# Controller-Board_Rack-PDU_1_0.net
KiCad netlist of a schematic drawn in EAGLE
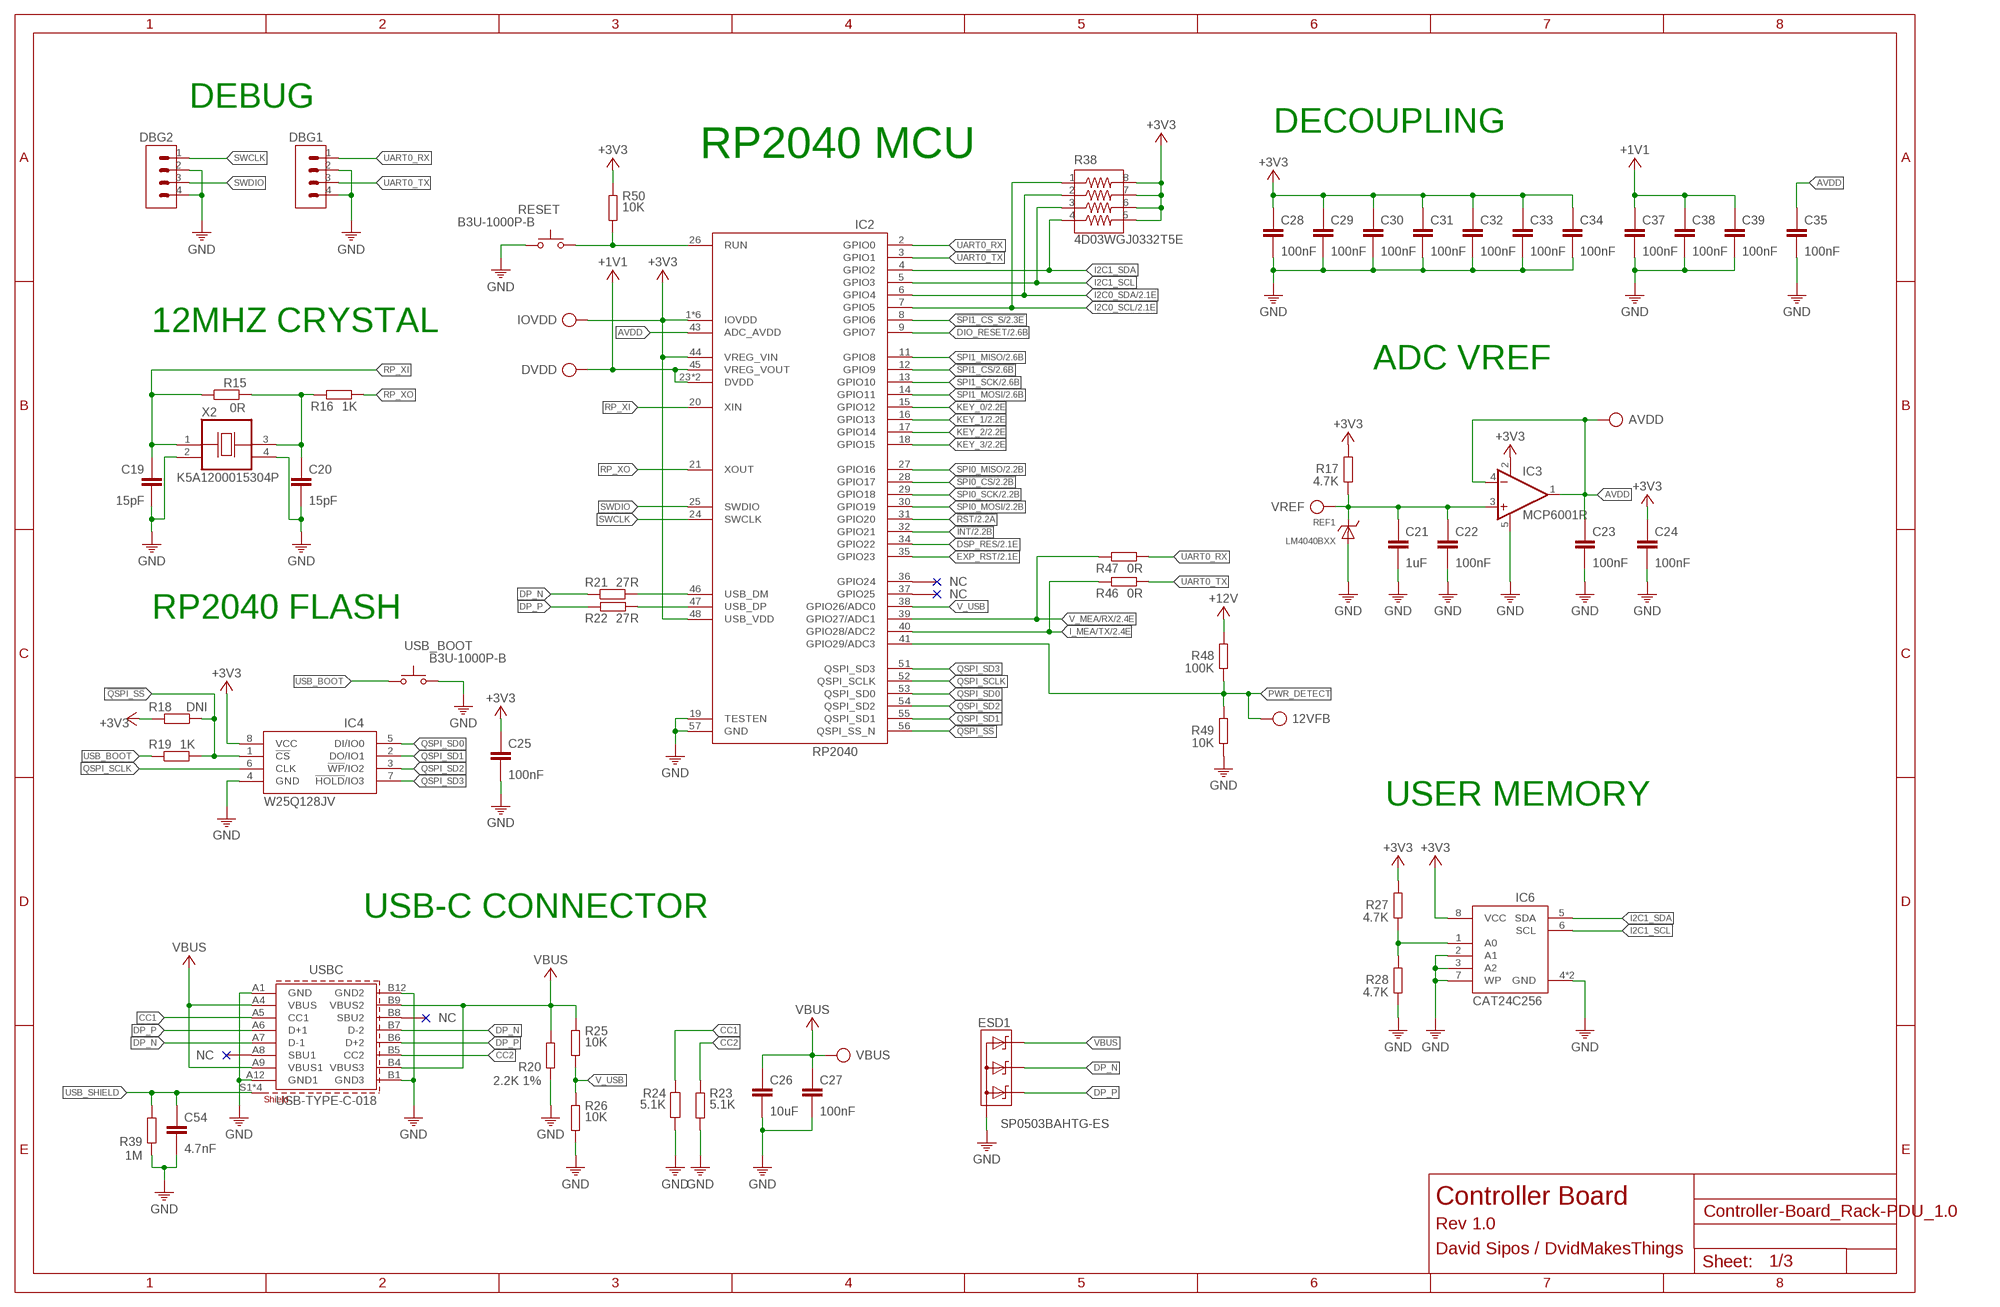
[diagram p0: schematic, sheet 1]
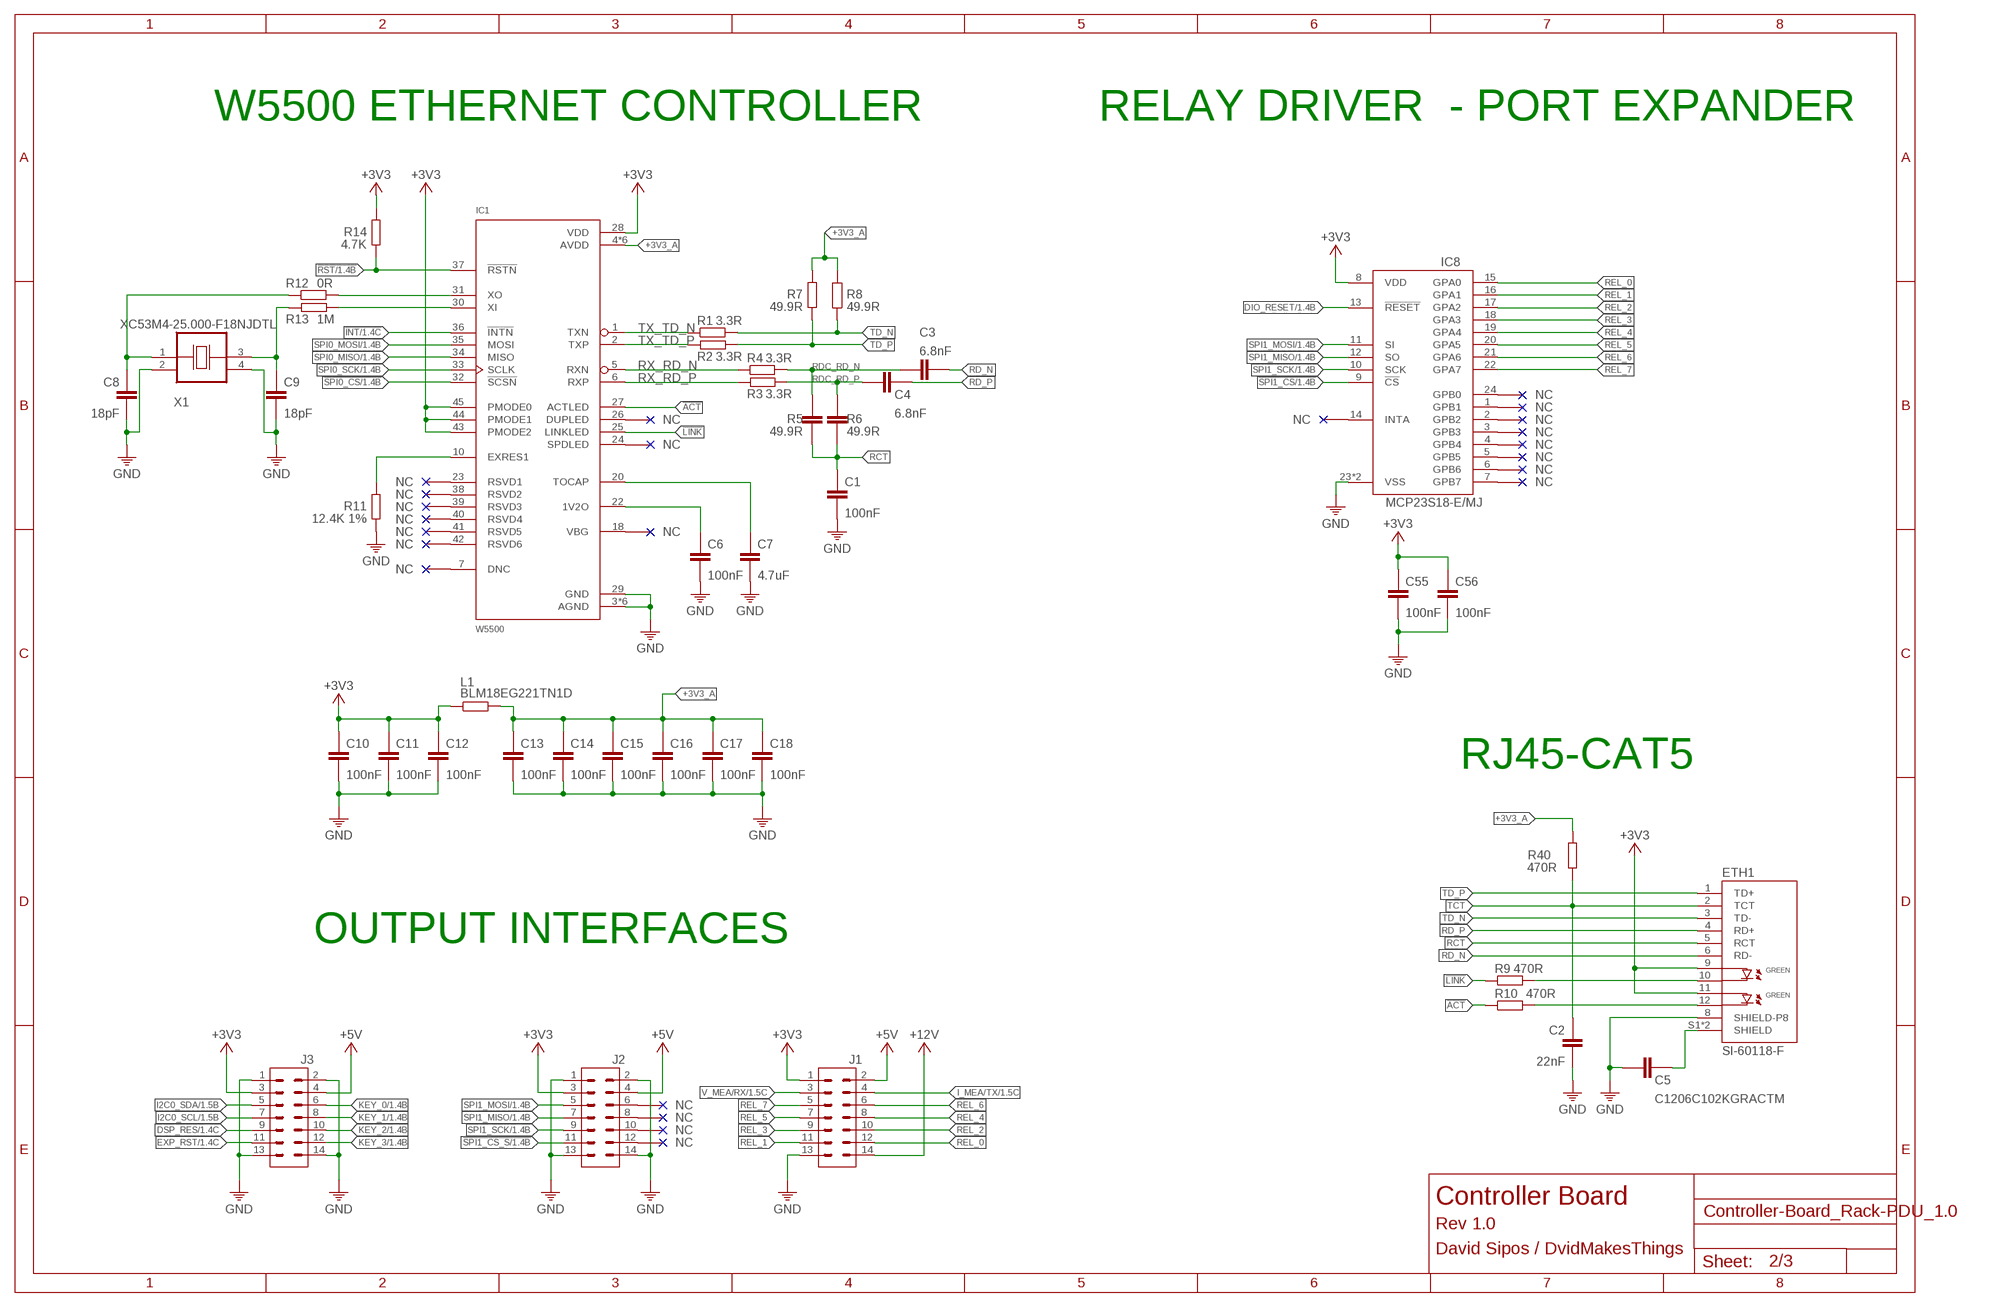
[diagram p1: schematic, sheet 2]
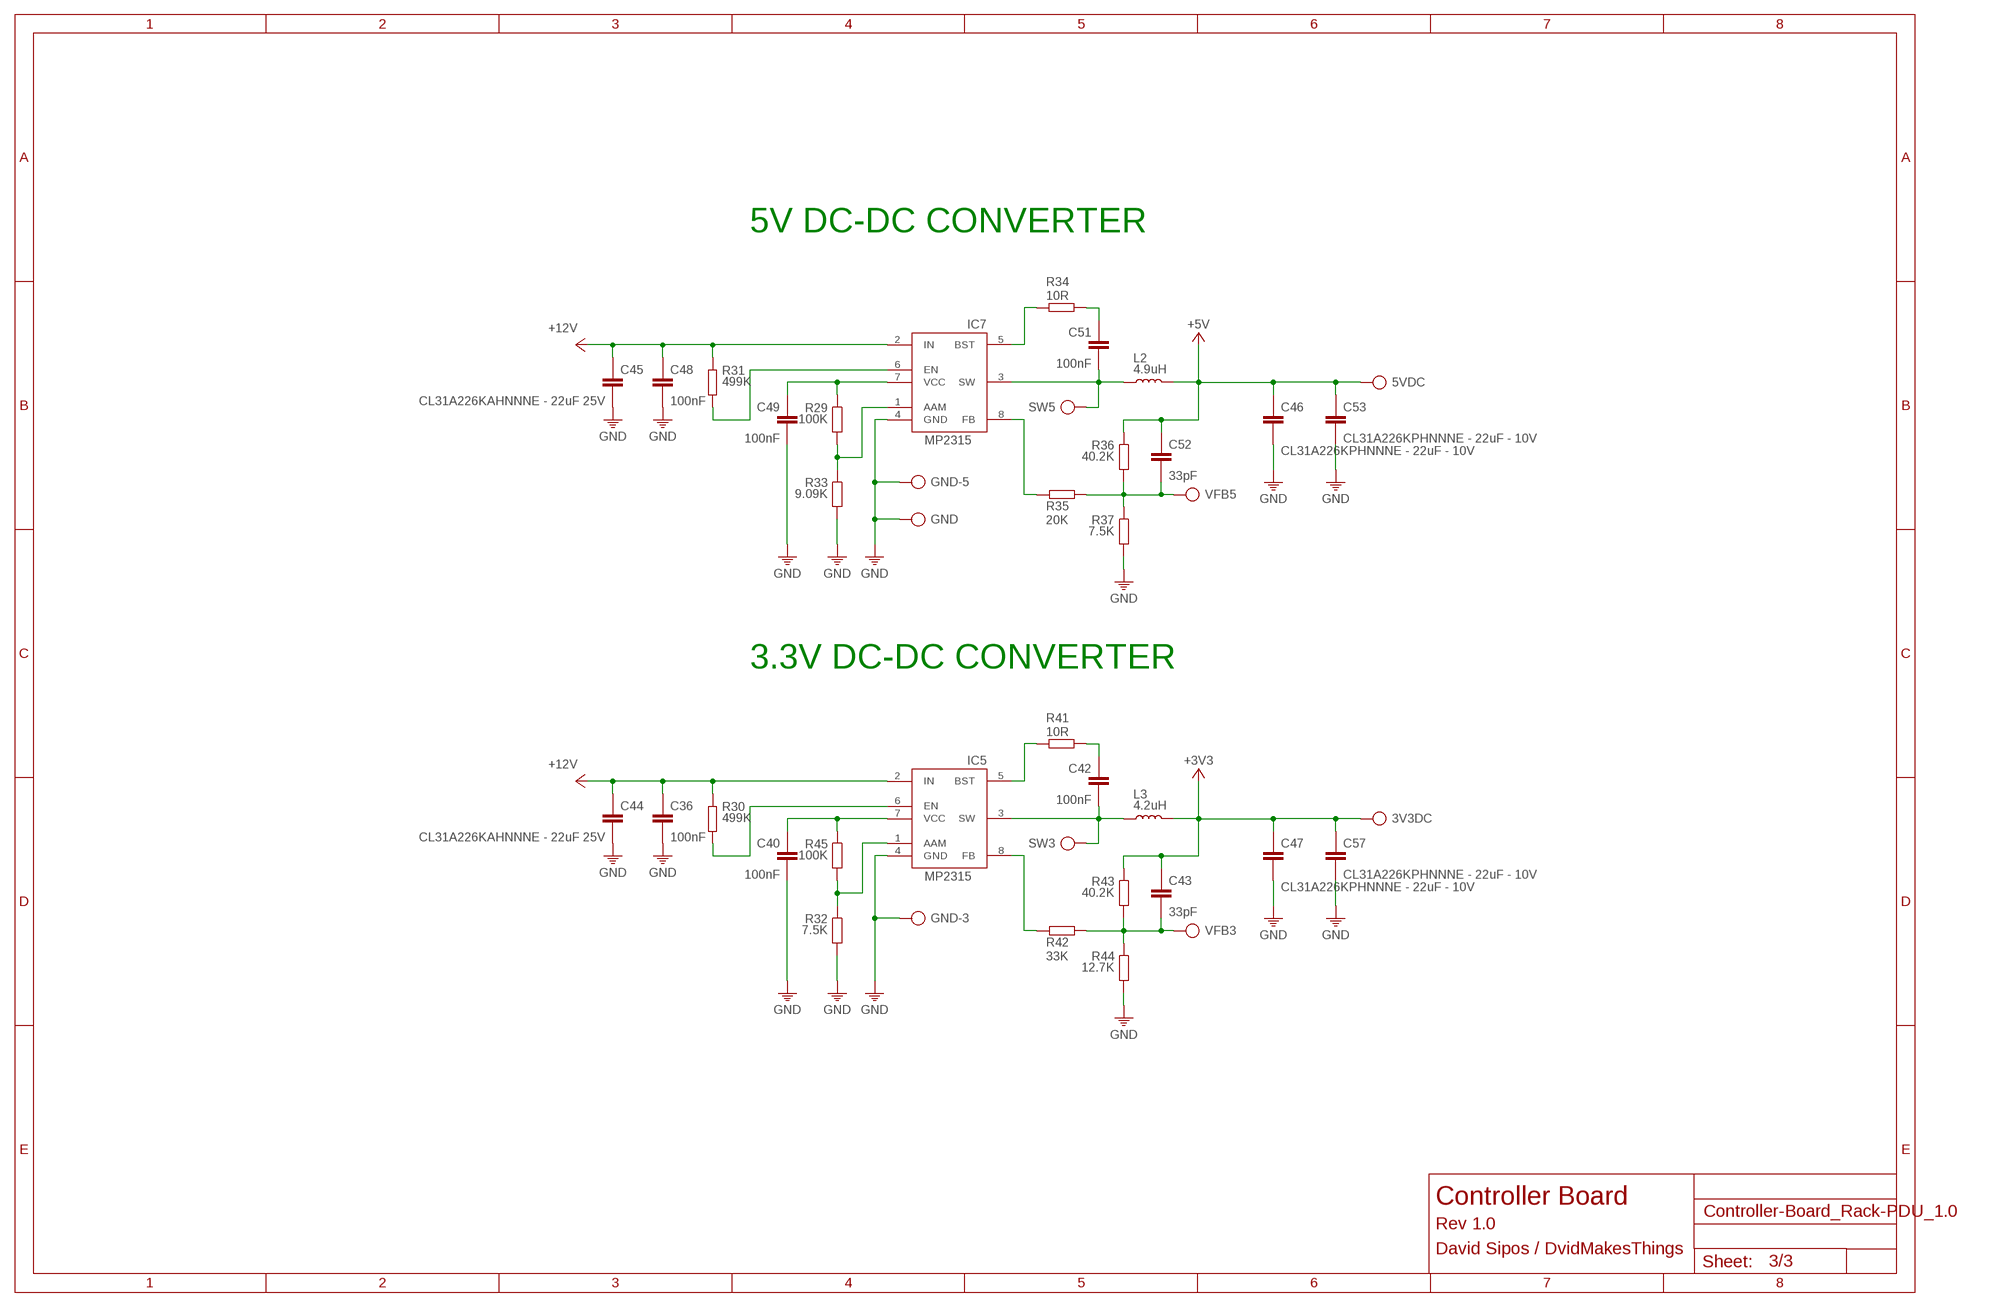
[diagram p2: schematic, sheet 3]

(export (version "E")
  (design (tool "Eeschema 10.0.6"))
  (components
    (comp (ref "C1")
      (value "100nF")
      (footprint "eagle-import:C0402")
      (libsource (lib "eagle-import") (part "C-0402"))
    )
    (comp (ref "C2")
      (value "22nF")
      (footprint "eagle-import:C0402")
      (libsource (lib "eagle-import") (part "C-0402"))
    )
    (comp (ref "C3")
      (value "6.8nF")
      (footprint "eagle-import:C0402")
      (libsource (lib "eagle-import") (part "C-0402"))
    )
    (comp (ref "C4")
      (value "6.8nF")
      (footprint "eagle-import:C0402")
      (libsource (lib "eagle-import") (part "C-0402"))
    )
    (comp (ref "C5")
      (value "C1206C102KGRACTM")
      (footprint "eagle-import:C1206")
      (libsource (lib "eagle-import") (part "C-1206"))
    )
    (comp (ref "C6")
      (value "100nF")
      (footprint "eagle-import:C0402")
      (libsource (lib "eagle-import") (part "C-0402"))
    )
    (comp (ref "C7")
      (value "4.7uF")
      (footprint "eagle-import:C0402")
      (libsource (lib "eagle-import") (part "C-0402"))
    )
    (comp (ref "C8")
      (value "18pF")
      (footprint "eagle-import:C0402")
      (libsource (lib "eagle-import") (part "C-0402"))
    )
    (comp (ref "C9")
      (value "18pF")
      (footprint "eagle-import:C0402")
      (libsource (lib "eagle-import") (part "C-0402"))
    )
    (comp (ref "C10")
      (value "100nF")
      (footprint "eagle-import:C0402")
      (libsource (lib "eagle-import") (part "C-0402"))
    )
    (comp (ref "C11")
      (value "100nF")
      (footprint "eagle-import:C0402")
      (libsource (lib "eagle-import") (part "C-0402"))
    )
    (comp (ref "C12")
      (value "100nF")
      (footprint "eagle-import:C0402")
      (libsource (lib "eagle-import") (part "C-0402"))
    )
    (comp (ref "C13")
      (value "100nF")
      (footprint "eagle-import:C0402")
      (libsource (lib "eagle-import") (part "C-0402"))
    )
    (comp (ref "C14")
      (value "100nF")
      (footprint "eagle-import:C0402")
      (libsource (lib "eagle-import") (part "C-0402"))
    )
    (comp (ref "C15")
      (value "100nF")
      (footprint "eagle-import:C0402")
      (libsource (lib "eagle-import") (part "C-0402"))
    )
    (comp (ref "C16")
      (value "100nF")
      (footprint "eagle-import:C0402")
      (libsource (lib "eagle-import") (part "C-0402"))
    )
    (comp (ref "C17")
      (value "100nF")
      (footprint "eagle-import:C0402")
      (libsource (lib "eagle-import") (part "C-0402"))
    )
    (comp (ref "C18")
      (value "100nF")
      (footprint "eagle-import:C0402")
      (libsource (lib "eagle-import") (part "C-0402"))
    )
    (comp (ref "C55")
      (value "100nF")
      (footprint "eagle-import:C0402")
      (libsource (lib "eagle-import") (part "C-0402"))
    )
    (comp (ref "C56")
      (value "100nF")
      (footprint "eagle-import:C0402")
      (libsource (lib "eagle-import") (part "C-0402"))
    )
    (comp (ref "ETH1")
      (value "SI-60118-F")
      (footprint "eagle-import:RJ45-CAT5")
      (fields (field (name "MANUFACTURER") "Bel Fuse"))
      (libsource (lib "eagle-import") (part "RJ45-CAT5"))
    )
    (comp (ref "IC1")
      (value "W5500")
      (footprint "eagle-import:LQFP48")
      (libsource (lib "eagle-import") (part "W5500"))
    )
    (comp (ref "IC8")
      (value "MCP23S18-E/MJ")
      (footprint "eagle-import:QFN50P400X400X100-25T265")
      (libsource (lib "eagle-import") (part "MCP23S18"))
    )
    (comp (ref "J1")
      (value "CON-2X7")
      (footprint "eagle-import:2X7")
      (libsource (lib "eagle-import") (part "CON-2X7"))
    )
    (comp (ref "J2")
      (value "CON-2X7")
      (footprint "eagle-import:2X7")
      (libsource (lib "eagle-import") (part "CON-2X7"))
    )
    (comp (ref "J3")
      (value "CON-2X7")
      (footprint "eagle-import:2X7")
      (libsource (lib "eagle-import") (part "CON-2X7"))
    )
    (comp (ref "L1")
      (value "BLM18EG221TN1D")
      (footprint "eagle-import:0603")
      (libsource (lib "eagle-import") (part "R0603"))
    )
    (comp (ref "R1")
      (value "3.3R")
      (footprint "eagle-import:0402")
      (libsource (lib "eagle-import") (part "R0402"))
    )
    (comp (ref "R2")
      (value "3.3R")
      (footprint "eagle-import:0402")
      (libsource (lib "eagle-import") (part "R0402"))
    )
    (comp (ref "R3")
      (value "3.3R")
      (footprint "eagle-import:0402")
      (libsource (lib "eagle-import") (part "R0402"))
    )
    (comp (ref "R4")
      (value "3.3R")
      (footprint "eagle-import:0402")
      (libsource (lib "eagle-import") (part "R0402"))
    )
    (comp (ref "R5")
      (value "49.9R")
      (footprint "eagle-import:C0402")
      (libsource (lib "eagle-import") (part "C-0402"))
    )
    (comp (ref "R6")
      (value "49.9R")
      (footprint "eagle-import:C0402")
      (libsource (lib "eagle-import") (part "C-0402"))
    )
    (comp (ref "R7")
      (value "49.9R")
      (footprint "eagle-import:0402")
      (libsource (lib "eagle-import") (part "R0402"))
    )
    (comp (ref "R8")
      (value "49.9R")
      (footprint "eagle-import:0402")
      (libsource (lib "eagle-import") (part "R0402"))
    )
    (comp (ref "R9")
      (value "470R")
      (footprint "eagle-import:0402")
      (libsource (lib "eagle-import") (part "R0402"))
    )
    (comp (ref "R10")
      (value "470R")
      (footprint "eagle-import:0402")
      (libsource (lib "eagle-import") (part "R0402"))
    )
    (comp (ref "R11")
      (value "12.4K 1%")
      (footprint "eagle-import:0402")
      (libsource (lib "eagle-import") (part "R0402"))
    )
    (comp (ref "R12")
      (value "0R")
      (footprint "eagle-import:0402")
      (libsource (lib "eagle-import") (part "R0402"))
    )
    (comp (ref "R13")
      (value "1M")
      (footprint "eagle-import:0402")
      (libsource (lib "eagle-import") (part "R0402"))
    )
    (comp (ref "R14")
      (value "4.7K")
      (footprint "eagle-import:0402")
      (libsource (lib "eagle-import") (part "R0402"))
    )
    (comp (ref "R40")
      (value "470R")
      (footprint "eagle-import:0402")
      (libsource (lib "eagle-import") (part "R0402"))
    )
    (comp (ref "X1")
      (value "XC53M4-25.000-F18NJDTL")
      (footprint "eagle-import:OSCCC500X320X130")
      (libsource (lib "eagle-import") (part "CRYSTAL"))
    )
    (comp (ref "12VFB")
      (value "TP")
      (footprint "eagle-import:TP")
      (libsource (lib "eagle-import") (part "TP"))
    )
    (comp (ref "AVDD")
      (value "TP")
      (footprint "eagle-import:TP")
      (libsource (lib "eagle-import") (part "TP"))
    )
    (comp (ref "C19")
      (value "15pF")
      (footprint "eagle-import:C0402")
      (libsource (lib "eagle-import") (part "C-0402"))
    )
    (comp (ref "C20")
      (value "15pF")
      (footprint "eagle-import:C0402")
      (libsource (lib "eagle-import") (part "C-0402"))
    )
    (comp (ref "C21")
      (value "1uF")
      (footprint "eagle-import:C0402")
      (libsource (lib "eagle-import") (part "C-0402"))
    )
    (comp (ref "C22")
      (value "100nF")
      (footprint "eagle-import:C0402")
      (libsource (lib "eagle-import") (part "C-0402"))
    )
    (comp (ref "C23")
      (value "100nF")
      (footprint "eagle-import:C0402")
      (libsource (lib "eagle-import") (part "C-0402"))
    )
    (comp (ref "C24")
      (value "100nF")
      (footprint "eagle-import:C0402")
      (libsource (lib "eagle-import") (part "C-0402"))
    )
    (comp (ref "C25")
      (value "100nF")
      (footprint "eagle-import:C0402")
      (libsource (lib "eagle-import") (part "C-0402"))
    )
    (comp (ref "C26")
      (value "10uF")
      (footprint "eagle-import:0805")
      (libsource (lib "eagle-import") (part "C0805"))
    )
    (comp (ref "C27")
      (value "100nF")
      (footprint "eagle-import:0402")
      (libsource (lib "eagle-import") (part "C0402"))
    )
    (comp (ref "C28")
      (value "100nF")
      (footprint "eagle-import:C0402")
      (libsource (lib "eagle-import") (part "C-0402"))
    )
    (comp (ref "C29")
      (value "100nF")
      (footprint "eagle-import:C0402")
      (libsource (lib "eagle-import") (part "C-0402"))
    )
    (comp (ref "C30")
      (value "100nF")
      (footprint "eagle-import:C0402")
      (libsource (lib "eagle-import") (part "C-0402"))
    )
    (comp (ref "C31")
      (value "100nF")
      (footprint "eagle-import:C0402")
      (libsource (lib "eagle-import") (part "C-0402"))
    )
    (comp (ref "C32")
      (value "100nF")
      (footprint "eagle-import:C0402")
      (libsource (lib "eagle-import") (part "C-0402"))
    )
    (comp (ref "C33")
      (value "100nF")
      (footprint "eagle-import:C0402")
      (libsource (lib "eagle-import") (part "C-0402"))
    )
    (comp (ref "C34")
      (value "100nF")
      (footprint "eagle-import:C0402")
      (libsource (lib "eagle-import") (part "C-0402"))
    )
    (comp (ref "C35")
      (value "100nF")
      (footprint "eagle-import:C0402")
      (libsource (lib "eagle-import") (part "C-0402"))
    )
    (comp (ref "C37")
      (value "100nF")
      (footprint "eagle-import:C0402")
      (libsource (lib "eagle-import") (part "C-0402"))
    )
    (comp (ref "C38")
      (value "100nF")
      (footprint "eagle-import:C0402")
      (libsource (lib "eagle-import") (part "C-0402"))
    )
    (comp (ref "C39")
      (value "100nF")
      (footprint "eagle-import:C0402")
      (libsource (lib "eagle-import") (part "C-0402"))
    )
    (comp (ref "C54")
      (value "4.7nF")
      (footprint "eagle-import:0402")
      (libsource (lib "eagle-import") (part "C0402"))
    )
    (comp (ref "DBG1")
      (value "CON-1X4")
      (footprint "eagle-import:1X4")
      (libsource (lib "eagle-import") (part "CON-1X4"))
    )
    (comp (ref "DBG2")
      (value "CON-1X4")
      (footprint "eagle-import:1X4")
      (libsource (lib "eagle-import") (part "CON-1X4"))
    )
    (comp (ref "DVDD")
      (value "TP")
      (footprint "eagle-import:TP")
      (libsource (lib "eagle-import") (part "TP"))
    )
    (comp (ref "ESD1")
      (value "SP0503BAHTG-ES")
      (footprint "eagle-import:SOT143")
      (libsource (lib "eagle-import") (part "SP0503BAHT"))
    )
    (comp (ref "IC2")
      (value "RP2040")
      (footprint "eagle-import:QFN40P700X700X100-57T510")
      (libsource (lib "eagle-import") (part "RP2040"))
    )
    (comp (ref "IC3")
      (value "MCP6001R")
      (footprint "eagle-import:SOT23-5")
      (libsource (lib "eagle-import") (part "MCP6001RT"))
    )
    (comp (ref "IC4")
      (value "W25Q128JVPIQ")
      (footprint "eagle-import:SON127P600X500X75-8N")
      (libsource (lib "eagle-import") (part "W25Q128JVP"))
    )
    (comp (ref "IC6")
      (value "CAT24C256HU4IGT3")
      (footprint "eagle-import:SON50P300X200X50-9T130X140N")
      (libsource (lib "eagle-import") (part "CAT24C256-HU4"))
    )
    (comp (ref "IOVDD")
      (value "TP")
      (footprint "eagle-import:TP")
      (libsource (lib "eagle-import") (part "TP"))
    )
    (comp (ref "R15")
      (value "0R")
      (footprint "eagle-import:0402")
      (libsource (lib "eagle-import") (part "R0402"))
    )
    (comp (ref "R16")
      (value "1K")
      (footprint "eagle-import:0402")
      (libsource (lib "eagle-import") (part "R0402"))
    )
    (comp (ref "R17")
      (value "4.7K")
      (footprint "eagle-import:0402")
      (libsource (lib "eagle-import") (part "R0402"))
    )
    (comp (ref "R18")
      (value "DNI")
      (footprint "eagle-import:0402")
      (libsource (lib "eagle-import") (part "R0402"))
    )
    (comp (ref "R19")
      (value "1K")
      (footprint "eagle-import:0402")
      (libsource (lib "eagle-import") (part "R0402"))
    )
    (comp (ref "R20")
      (value "2.2K 1%")
      (footprint "eagle-import:0402")
      (libsource (lib "eagle-import") (part "ds_passive_46685041_R0402"))
    )
    (comp (ref "R21")
      (value "27R")
      (footprint "eagle-import:0402")
      (libsource (lib "eagle-import") (part "R0402"))
    )
    (comp (ref "R22")
      (value "27R")
      (footprint "eagle-import:0402")
      (libsource (lib "eagle-import") (part "R0402"))
    )
    (comp (ref "R23")
      (value "5.1K")
      (footprint "eagle-import:0402")
      (libsource (lib "eagle-import") (part "ds_passive_46685041_R0402"))
    )
    (comp (ref "R24")
      (value "5.1K")
      (footprint "eagle-import:0402")
      (libsource (lib "eagle-import") (part "ds_passive_46685041_R0402"))
    )
    (comp (ref "R25")
      (value "10K")
      (footprint "eagle-import:0402")
      (libsource (lib "eagle-import") (part "ds_passive_46685041_R0402"))
    )
    (comp (ref "R26")
      (value "10K")
      (footprint "eagle-import:0402")
      (libsource (lib "eagle-import") (part "ds_passive_46685041_R0402"))
    )
    (comp (ref "R27")
      (value "4.7K")
      (footprint "eagle-import:0402")
      (libsource (lib "eagle-import") (part "R0402"))
    )
    (comp (ref "R28")
      (value "4.7K")
      (footprint "eagle-import:0402")
      (libsource (lib "eagle-import") (part "R0402"))
    )
    (comp (ref "R38")
      (value "4D03WGJ0332T5E")
      (footprint "eagle-import:742C083103JP")
      (fields
        (field (name "MANUFACTURER") "CTS Resistor Products")
        (field (name "MPN") "742C083103JP")
        (field (name "CREATED_BY") "PCBLayout.com")
      )
      (libsource (lib "eagle-import") (part "742C083103JP"))
    )
    (comp (ref "R39")
      (value "1M")
      (footprint "eagle-import:0402")
      (libsource (lib "eagle-import") (part "ds_passive_46685041_R0402"))
    )
    (comp (ref "R46")
      (value "0R")
      (footprint "eagle-import:0402")
      (libsource (lib "eagle-import") (part "R0402"))
    )
    (comp (ref "R47")
      (value "0R")
      (footprint "eagle-import:0402")
      (libsource (lib "eagle-import") (part "R0402"))
    )
    (comp (ref "R48")
      (value "100K")
      (footprint "eagle-import:0402")
      (libsource (lib "eagle-import") (part "R0402"))
    )
    (comp (ref "R49")
      (value "10K")
      (footprint "eagle-import:0402")
      (libsource (lib "eagle-import") (part "R0402"))
    )
    (comp (ref "R50")
      (value "10K")
      (footprint "eagle-import:0402")
      (libsource (lib "eagle-import") (part "ds_passive_46685041_R0402"))
    )
    (comp (ref "REF1")
      (value "LM4040BXX")
      (footprint "eagle-import:SOT23")
      (libsource (lib "eagle-import") (part "LM4040BXX"))
    )
    (comp (ref "RESET")
      (value "B3U-1000P-B")
      (footprint "eagle-import:SWITCH-OMRON_B3U-1000P")
      (libsource (lib "eagle-import") (part "SWITCH-OMRON_B3U-1000P"))
    )
    (comp (ref "USBC")
      (value "USB-TYPE-C-018")
      (footprint "eagle-import:629722000214")
      (libsource (lib "eagle-import") (part "629722000214"))
    )
    (comp (ref "USB_BOOT")
      (value "B3U-1000P-B")
      (footprint "eagle-import:SWITCH-OMRON_B3U-1000P")
      (libsource (lib "eagle-import") (part "SWITCH-OMRON_B3U-1000P"))
    )
    (comp (ref "VBUS")
      (value "TP")
      (footprint "eagle-import:TP")
      (libsource (lib "eagle-import") (part "TP"))
    )
    (comp (ref "VREF")
      (value "TP")
      (footprint "eagle-import:TP")
      (libsource (lib "eagle-import") (part "TP"))
    )
    (comp (ref "X2")
      (value "K5A1200015304P")
      (footprint "eagle-import:OSCCC500X320X130")
      (libsource (lib "eagle-import") (part "CRYSTAL"))
    )
    (comp (ref "3V3DC")
      (value "TP")
      (footprint "eagle-import:TP")
      (libsource (lib "eagle-import") (part "TP"))
    )
    (comp (ref "5VDC")
      (value "TP")
      (footprint "eagle-import:TP")
      (libsource (lib "eagle-import") (part "TP"))
    )
    (comp (ref "C36")
      (value "100nF")
      (footprint "eagle-import:0402")
      (libsource (lib "eagle-import") (part "C0402"))
    )
    (comp (ref "C40")
      (value "100nF")
      (footprint "eagle-import:0402")
      (libsource (lib "eagle-import") (part "C0402"))
    )
    (comp (ref "C42")
      (value "100nF")
      (footprint "eagle-import:0402")
      (libsource (lib "eagle-import") (part "C0402"))
    )
    (comp (ref "C43")
      (value "33pF")
      (footprint "eagle-import:0402")
      (libsource (lib "eagle-import") (part "C0402"))
    )
    (comp (ref "C44")
      (value "CL31A226KAHNNNE - 22uF 25V")
      (footprint "eagle-import:C1206")
      (libsource (lib "eagle-import") (part "C-1206"))
    )
    (comp (ref "C45")
      (value "CL31A226KAHNNNE - 22uF 25V")
      (footprint "eagle-import:C1206")
      (libsource (lib "eagle-import") (part "C-1206"))
    )
    (comp (ref "C46")
      (value "CL31A226KPHNNNE - 22uF - 10V")
      (footprint "eagle-import:C1206")
      (libsource (lib "eagle-import") (part "C-1206"))
    )
    (comp (ref "C47")
      (value "CL31A226KPHNNNE - 22uF - 10V")
      (footprint "eagle-import:C1206")
      (libsource (lib "eagle-import") (part "C-1206"))
    )
    (comp (ref "C48")
      (value "100nF")
      (footprint "eagle-import:0402")
      (libsource (lib "eagle-import") (part "C0402"))
    )
    (comp (ref "C49")
      (value "100nF")
      (footprint "eagle-import:0402")
      (libsource (lib "eagle-import") (part "C0402"))
    )
    (comp (ref "C51")
      (value "100nF")
      (footprint "eagle-import:0402")
      (libsource (lib "eagle-import") (part "C0402"))
    )
    (comp (ref "C52")
      (value "33pF")
      (footprint "eagle-import:0402")
      (libsource (lib "eagle-import") (part "C0402"))
    )
    (comp (ref "C53")
      (value "CL31A226KPHNNNE - 22uF - 10V")
      (footprint "eagle-import:C1206")
      (libsource (lib "eagle-import") (part "C-1206"))
    )
    (comp (ref "C57")
      (value "CL31A226KPHNNNE - 22uF - 10V")
      (footprint "eagle-import:C1206")
      (libsource (lib "eagle-import") (part "C-1206"))
    )
    (comp (ref "GND") (value "TP") (footprint "eagle-import:TP") (libsource (lib "eagle-import") (part "TP")))
    (comp (ref "GND-3")
      (value "TP")
      (footprint "eagle-import:TP")
      (libsource (lib "eagle-import") (part "TP"))
    )
    (comp (ref "GND-5")
      (value "TP")
      (footprint "eagle-import:TP")
      (libsource (lib "eagle-import") (part "TP"))
    )
    (comp (ref "IC5")
      (value "MP2315S")
      (footprint "eagle-import:SOT65P280X110-8N")
      (libsource (lib "eagle-import") (part "MP2315TSOT23-8"))
    )
    (comp (ref "IC7")
      (value "MP2315GJ-Z")
      (footprint "eagle-import:SOT65P280X110-8N")
      (libsource (lib "eagle-import") (part "MP2315TSOT23-8"))
    )
    (comp (ref "L2")
      (value "4.9uH")
      (footprint "eagle-import:SRR5228A")
      (libsource (lib "eagle-import") (part "L"))
    )
    (comp (ref "L3")
      (value "4.2uH")
      (footprint "eagle-import:SRR5228A")
      (libsource (lib "eagle-import") (part "L"))
    )
    (comp (ref "R29")
      (value "100K")
      (footprint "eagle-import:0402")
      (libsource (lib "eagle-import") (part "R0402"))
    )
    (comp (ref "R30")
      (value "499K")
      (footprint "eagle-import:0402")
      (libsource (lib "eagle-import") (part "R0402"))
    )
    (comp (ref "R31")
      (value "499K")
      (footprint "eagle-import:0402")
      (libsource (lib "eagle-import") (part "R0402"))
    )
    (comp (ref "R32")
      (value "7.5K")
      (footprint "eagle-import:0402")
      (libsource (lib "eagle-import") (part "R0402"))
    )
    (comp (ref "R33")
      (value "9.09K")
      (footprint "eagle-import:0402")
      (libsource (lib "eagle-import") (part "R0402"))
    )
    (comp (ref "R34")
      (value "10R")
      (footprint "eagle-import:0402")
      (libsource (lib "eagle-import") (part "R0402"))
    )
    (comp (ref "R35")
      (value "20K")
      (footprint "eagle-import:0402")
      (libsource (lib "eagle-import") (part "R0402"))
    )
    (comp (ref "R36")
      (value "40.2K")
      (footprint "eagle-import:0402")
      (libsource (lib "eagle-import") (part "R0402"))
    )
    (comp (ref "R37")
      (value "7.5K")
      (footprint "eagle-import:0402")
      (libsource (lib "eagle-import") (part "R0402"))
    )
    (comp (ref "R41")
      (value "10R")
      (footprint "eagle-import:0402")
      (libsource (lib "eagle-import") (part "R0402"))
    )
    (comp (ref "R42")
      (value "33K")
      (footprint "eagle-import:0402")
      (libsource (lib "eagle-import") (part "R0402"))
    )
    (comp (ref "R43")
      (value "40.2K")
      (footprint "eagle-import:0402")
      (libsource (lib "eagle-import") (part "R0402"))
    )
    (comp (ref "R44")
      (value "12.7K")
      (footprint "eagle-import:0402")
      (libsource (lib "eagle-import") (part "R0402"))
    )
    (comp (ref "R45")
      (value "100K")
      (footprint "eagle-import:0402")
      (libsource (lib "eagle-import") (part "R0402"))
    )
    (comp (ref "SW3") (value "TP") (footprint "eagle-import:TP") (libsource (lib "eagle-import") (part "TP")))
    (comp (ref "SW5") (value "TP") (footprint "eagle-import:TP") (libsource (lib "eagle-import") (part "TP")))
    (comp (ref "VFB3")
      (value "TP")
      (footprint "eagle-import:TP")
      (libsource (lib "eagle-import") (part "TP"))
    )
    (comp (ref "VFB5")
      (value "TP")
      (footprint "eagle-import:TP")
      (libsource (lib "eagle-import") (part "TP"))
    )
  )
  (nets
    (net (code "1") (name "+1V1") (class "Default")
      (node (ref "C37") (pin "1") (pinfunction "1_1") (pintype "passive"))
      (node (ref "C38") (pin "1") (pinfunction "1_1") (pintype "passive"))
      (node (ref "C39") (pin "1") (pinfunction "1_1") (pintype "passive"))
      (node (ref "DVDD") (pin "TP") (pinfunction "P$1_TP") (pintype "bidirectional"))
      (node (ref "IC2") (pin "23") (pinfunction "DVDD_23") (pintype "bidirectional"))
      (node (ref "IC2") (pin "45") (pinfunction "VREG_VOUT_45") (pintype "bidirectional"))
      (node (ref "IC2") (pin "50") (pinfunction "DVDD_50") (pintype "bidirectional"))
    )
    (net (code "2") (name "+3V3") (class "Default")
      (node (ref "3V3DC") (pin "TP") (pinfunction "P$1_TP") (pintype "bidirectional"))
      (node (ref "C10") (pin "1") (pinfunction "1_1") (pintype "passive"))
      (node (ref "C11") (pin "1") (pinfunction "1_1") (pintype "passive"))
      (node (ref "C12") (pin "1") (pinfunction "1_1") (pintype "passive"))
      (node (ref "C24") (pin "1") (pinfunction "1_1") (pintype "passive"))
      (node (ref "C25") (pin "1") (pinfunction "1_1") (pintype "passive"))
      (node (ref "C28") (pin "1") (pinfunction "1_1") (pintype "passive"))
      (node (ref "C29") (pin "1") (pinfunction "1_1") (pintype "passive"))
      (node (ref "C30") (pin "1") (pinfunction "1_1") (pintype "passive"))
      (node (ref "C31") (pin "1") (pinfunction "1_1") (pintype "passive"))
      (node (ref "C32") (pin "1") (pinfunction "1_1") (pintype "passive"))
      (node (ref "C33") (pin "1") (pinfunction "1_1") (pintype "passive"))
      (node (ref "C34") (pin "1") (pinfunction "1_1") (pintype "passive"))
      (node (ref "C43") (pin "1") (pinfunction "1_1") (pintype "passive"))
      (node (ref "C47") (pin "1") (pinfunction "1_1") (pintype "passive"))
      (node (ref "C55") (pin "1") (pinfunction "1_1") (pintype "passive"))
      (node (ref "C56") (pin "1") (pinfunction "1_1") (pintype "passive"))
      (node (ref "C57") (pin "1") (pinfunction "1_1") (pintype "passive"))
      (node (ref "ETH1") (pin "11") (pinfunction "GA2_11") (pintype "passive"))
      (node (ref "ETH1") (pin "9") (pinfunction "GA1_9") (pintype "passive"))
      (node (ref "IC1") (pin "28") (pinfunction "VDD_28") (pintype "power_in"))
      (node (ref "IC1") (pin "43") (pinfunction "PMODE2_43") (pintype "input"))
      (node (ref "IC1") (pin "44") (pinfunction "PMODE1_44") (pintype "input"))
      (node (ref "IC1") (pin "45") (pinfunction "PMODE0_45") (pintype "input"))
      (node (ref "IC2") (pin "1") (pinfunction "IOVDD_1") (pintype "bidirectional"))
      (node (ref "IC2") (pin "10") (pinfunction "IOVDD_10") (pintype "bidirectional"))
      (node (ref "IC2") (pin "22") (pinfunction "IOVDD_22") (pintype "bidirectional"))
      (node (ref "IC2") (pin "33") (pinfunction "IOVDD_33") (pintype "bidirectional"))
      (node (ref "IC2") (pin "42") (pinfunction "IOVDD_42") (pintype "bidirectional"))
      (node (ref "IC2") (pin "44") (pinfunction "VREG_VIN_44") (pintype "bidirectional"))
      (node (ref "IC2") (pin "48") (pinfunction "USB_VDD_48") (pintype "bidirectional"))
      (node (ref "IC2") (pin "49") (pinfunction "IOVDD_49") (pintype "bidirectional"))
      (node (ref "IC3") (pin "2") (pinfunction "V+_2") (pintype "power_in"))
      (node (ref "IC4") (pin "8") (pinfunction "VCC_8") (pintype "power_in"))
      (node (ref "IC6") (pin "8") (pinfunction "VCC_8") (pintype "power_in"))
      (node (ref "IC8") (pin "8") (pinfunction "VDD_8") (pintype "power_in"))
      (node (ref "IOVDD") (pin "TP") (pinfunction "P$1_TP") (pintype "bidirectional"))
      (node (ref "J1") (pin "1") (pinfunction "1_1") (pintype "bidirectional"))
      (node (ref "J2") (pin "3") (pinfunction "3_3") (pintype "bidirectional"))
      (node (ref "J3") (pin "3") (pinfunction "3_3") (pintype "bidirectional"))
      (node (ref "L1") (pin "1") (pinfunction "1_1") (pintype "passive"))
      (node (ref "L3") (pin "2") (pinfunction "2_2") (pintype "passive"))
      (node (ref "R14") (pin "2") (pinfunction "2_2") (pintype "passive"))
      (node (ref "R17") (pin "2") (pinfunction "2_2") (pintype "passive"))
      (node (ref "R18") (pin "2") (pinfunction "2_2") (pintype "passive"))
      (node (ref "R27") (pin "2") (pinfunction "2_2") (pintype "passive"))
      (node (ref "R38") (pin "5") (pinfunction "5_5") (pintype "passive"))
      (node (ref "R38") (pin "6") (pinfunction "6_6") (pintype "passive"))
      (node (ref "R38") (pin "7") (pinfunction "7_7") (pintype "passive"))
      (node (ref "R38") (pin "8") (pinfunction "8_8") (pintype "passive"))
      (node (ref "R43") (pin "1") (pinfunction "1_1") (pintype "passive"))
      (node (ref "R50") (pin "1") (pinfunction "1_1") (pintype "passive"))
    )
    (net (code "3") (name "+3V3_A") (class "Default")
      (node (ref "C13") (pin "1") (pinfunction "1_1") (pintype "passive"))
      (node (ref "C14") (pin "1") (pinfunction "1_1") (pintype "passive"))
      (node (ref "C15") (pin "1") (pinfunction "1_1") (pintype "passive"))
      (node (ref "C16") (pin "1") (pinfunction "1_1") (pintype "passive"))
      (node (ref "C17") (pin "1") (pinfunction "1_1") (pintype "passive"))
      (node (ref "C18") (pin "1") (pinfunction "1_1") (pintype "passive"))
      (node (ref "IC1") (pin "11") (pinfunction "AVDD_11") (pintype "power_in"))
      (node (ref "IC1") (pin "15") (pinfunction "AVDD_15") (pintype "power_in"))
      (node (ref "IC1") (pin "17") (pinfunction "AVDD_17") (pintype "power_in"))
      (node (ref "IC1") (pin "21") (pinfunction "AVDD_21") (pintype "power_in"))
      (node (ref "IC1") (pin "4") (pinfunction "AVDD_4") (pintype "power_in"))
      (node (ref "IC1") (pin "8") (pinfunction "AVDD_8") (pintype "power_in"))
      (node (ref "L1") (pin "2") (pinfunction "2_2") (pintype "passive"))
      (node (ref "R40") (pin "2") (pinfunction "2_2") (pintype "passive"))
      (node (ref "R7") (pin "2") (pinfunction "2_2") (pintype "passive"))
      (node (ref "R8") (pin "2") (pinfunction "2_2") (pintype "passive"))
    )
    (net (code "4") (name "+5V") (class "Default")
      (node (ref "5VDC") (pin "TP") (pinfunction "P$1_TP") (pintype "bidirectional"))
      (node (ref "C46") (pin "1") (pinfunction "1_1") (pintype "passive"))
      (node (ref "C52") (pin "1") (pinfunction "1_1") (pintype "passive"))
      (node (ref "C53") (pin "1") (pinfunction "1_1") (pintype "passive"))
      (node (ref "J1") (pin "2") (pinfunction "2_2") (pintype "bidirectional"))
      (node (ref "J2") (pin "4") (pinfunction "4_4") (pintype "bidirectional"))
      (node (ref "J3") (pin "4") (pinfunction "4_4") (pintype "bidirectional"))
      (node (ref "L2") (pin "2") (pinfunction "2_2") (pintype "passive"))
      (node (ref "R36") (pin "1") (pinfunction "1_1") (pintype "passive"))
    )
    (net (code "5") (name "+12V") (class "Default")
      (node (ref "C36") (pin "1") (pinfunction "1_1") (pintype "passive"))
      (node (ref "C44") (pin "1") (pinfunction "1_1") (pintype "passive"))
      (node (ref "C45") (pin "1") (pinfunction "1_1") (pintype "passive"))
      (node (ref "C48") (pin "1") (pinfunction "1_1") (pintype "passive"))
      (node (ref "IC5") (pin "2") (pinfunction "IN_2") (pintype "bidirectional"))
      (node (ref "IC7") (pin "2") (pinfunction "IN_2") (pintype "bidirectional"))
      (node (ref "J1") (pin "14") (pinfunction "14_14") (pintype "bidirectional"))
      (node (ref "R30") (pin "1") (pinfunction "1_1") (pintype "passive"))
      (node (ref "R31") (pin "1") (pinfunction "1_1") (pintype "passive"))
      (node (ref "R48") (pin "2") (pinfunction "2_2") (pintype "passive"))
    )
    (net (code "6") (name "AVDD") (class "Default")
      (node (ref "AVDD") (pin "TP") (pinfunction "P$1_TP") (pintype "bidirectional"))
      (node (ref "C23") (pin "1") (pinfunction "1_1") (pintype "passive"))
      (node (ref "C35") (pin "1") (pinfunction "1_1") (pintype "passive"))
      (node (ref "IC2") (pin "43") (pinfunction "ADC_AVDD_43") (pintype "bidirectional"))
      (node (ref "IC3") (pin "1") (pinfunction "OUT_1") (pintype "output"))
      (node (ref "IC3") (pin "4") (pinfunction "-IN_4") (pintype "input"))
    )
    (net (code "7") (name "CC1") (class "Default")
      (node (ref "R24") (pin "1") (pinfunction "1_1") (pintype "passive"))
      (node (ref "USBC") (pin "A5") (pinfunction "CC1_A5") (pintype "passive"))
    )
    (net (code "8") (name "CC2") (class "Default")
      (node (ref "R23") (pin "1") (pinfunction "1_1") (pintype "passive"))
      (node (ref "USBC") (pin "B5") (pinfunction "CC2_B5") (pintype "passive"))
    )
    (net (code "9") (name "DIO_RESET") (class "Default")
      (node (ref "IC2") (pin "9") (pinfunction "GPIO7_9") (pintype "bidirectional"))
      (node (ref "IC8") (pin "13") (pinfunction "~{RESET}_13") (pintype "input"))
    )
    (net (code "10") (name "DP_N") (class "Default")
      (node (ref "ESD1") (pin "3") (pinfunction "C2_3") (pintype "bidirectional"))
      (node (ref "R21") (pin "1") (pinfunction "1_1") (pintype "passive"))
      (node (ref "USBC") (pin "A7") (pinfunction "D-1_A7") (pintype "passive"))
      (node (ref "USBC") (pin "B7") (pinfunction "D-2_B7") (pintype "passive"))
    )
    (net (code "11") (name "DP_P") (class "Default")
      (node (ref "ESD1") (pin "2") (pinfunction "C1_2") (pintype "bidirectional"))
      (node (ref "R22") (pin "1") (pinfunction "1_1") (pintype "passive"))
      (node (ref "USBC") (pin "A6") (pinfunction "D+1_A6") (pintype "passive"))
      (node (ref "USBC") (pin "B6") (pinfunction "D+2_B6") (pintype "passive"))
    )
    (net (code "12") (name "DSP_RES") (class "Default")
      (node (ref "IC2") (pin "34") (pinfunction "GPIO22_34") (pintype "bidirectional"))
      (node (ref "J3") (pin "9") (pinfunction "9_9") (pintype "bidirectional"))
    )
    (net (code "13") (name "EXP_RST") (class "Default")
      (node (ref "IC2") (pin "35") (pinfunction "GPIO23_35") (pintype "bidirectional"))
      (node (ref "J3") (pin "11") (pinfunction "11_11") (pintype "bidirectional"))
    )
    (net (code "14") (name "GND") (class "Default")
      (node (ref "C1") (pin "2") (pinfunction "2_2") (pintype "passive"))
      (node (ref "C10") (pin "2") (pinfunction "2_2") (pintype "passive"))
      (node (ref "C11") (pin "2") (pinfunction "2_2") (pintype "passive"))
      (node (ref "C12") (pin "2") (pinfunction "2_2") (pintype "passive"))
      (node (ref "C13") (pin "2") (pinfunction "2_2") (pintype "passive"))
      (node (ref "C14") (pin "2") (pinfunction "2_2") (pintype "passive"))
      (node (ref "C15") (pin "2") (pinfunction "2_2") (pintype "passive"))
      (node (ref "C16") (pin "2") (pinfunction "2_2") (pintype "passive"))
      (node (ref "C17") (pin "2") (pinfunction "2_2") (pintype "passive"))
      (node (ref "C18") (pin "2") (pinfunction "2_2") (pintype "passive"))
      (node (ref "C19") (pin "2") (pinfunction "2_2") (pintype "passive"))
      (node (ref "C2") (pin "2") (pinfunction "2_2") (pintype "passive"))
      (node (ref "C20") (pin "2") (pinfunction "2_2") (pintype "passive"))
      (node (ref "C21") (pin "2") (pinfunction "2_2") (pintype "passive"))
      (node (ref "C22") (pin "2") (pinfunction "2_2") (pintype "passive"))
      (node (ref "C23") (pin "2") (pinfunction "2_2") (pintype "passive"))
      (node (ref "C24") (pin "2") (pinfunction "2_2") (pintype "passive"))
      (node (ref "C25") (pin "2") (pinfunction "2_2") (pintype "passive"))
      (node (ref "C26") (pin "2") (pinfunction "2_2") (pintype "passive"))
      (node (ref "C27") (pin "2") (pinfunction "2_2") (pintype "passive"))
      (node (ref "C28") (pin "2") (pinfunction "2_2") (pintype "passive"))
      (node (ref "C29") (pin "2") (pinfunction "2_2") (pintype "passive"))
      (node (ref "C30") (pin "2") (pinfunction "2_2") (pintype "passive"))
      (node (ref "C31") (pin "2") (pinfunction "2_2") (pintype "passive"))
      (node (ref "C32") (pin "2") (pinfunction "2_2") (pintype "passive"))
      (node (ref "C33") (pin "2") (pinfunction "2_2") (pintype "passive"))
      (node (ref "C34") (pin "2") (pinfunction "2_2") (pintype "passive"))
      (node (ref "C35") (pin "2") (pinfunction "2_2") (pintype "passive"))
      (node (ref "C36") (pin "2") (pinfunction "2_2") (pintype "passive"))
      (node (ref "C37") (pin "2") (pinfunction "2_2") (pintype "passive"))
      (node (ref "C38") (pin "2") (pinfunction "2_2") (pintype "passive"))
      (node (ref "C39") (pin "2") (pinfunction "2_2") (pintype "passive"))
      (node (ref "C40") (pin "2") (pinfunction "2_2") (pintype "passive"))
      (node (ref "C44") (pin "2") (pinfunction "2_2") (pintype "passive"))
      (node (ref "C45") (pin "2") (pinfunction "2_2") (pintype "passive"))
      (node (ref "C46") (pin "2") (pinfunction "2_2") (pintype "passive"))
      (node (ref "C47") (pin "2") (pinfunction "2_2") (pintype "passive"))
      (node (ref "C48") (pin "2") (pinfunction "2_2") (pintype "passive"))
      (node (ref "C49") (pin "2") (pinfunction "2_2") (pintype "passive"))
      (node (ref "C5") (pin "1") (pinfunction "1_1") (pintype "passive"))
      (node (ref "C53") (pin "2") (pinfunction "2_2") (pintype "passive"))
      (node (ref "C54") (pin "2") (pinfunction "2_2") (pintype "passive"))
      (node (ref "C55") (pin "2") (pinfunction "2_2") (pintype "passive"))
      (node (ref "C56") (pin "2") (pinfunction "2_2") (pintype "passive"))
      (node (ref "C57") (pin "2") (pinfunction "2_2") (pintype "passive"))
      (node (ref "C6") (pin "2") (pinfunction "2_2") (pintype "passive"))
      (node (ref "C7") (pin "2") (pinfunction "2_2") (pintype "passive"))
      (node (ref "C8") (pin "2") (pinfunction "2_2") (pintype "passive"))
      (node (ref "C9") (pin "2") (pinfunction "2_2") (pintype "passive"))
      (node (ref "DBG1") (pin "2") (pinfunction "P$2_2") (pintype "bidirectional"))
      (node (ref "DBG1") (pin "4") (pinfunction "P$4_4") (pintype "bidirectional"))
      (node (ref "DBG2") (pin "2") (pinfunction "P$2_2") (pintype "bidirectional"))
      (node (ref "DBG2") (pin "4") (pinfunction "P$4_4") (pintype "bidirectional"))
      (node (ref "ESD1") (pin "1") (pinfunction "A_1") (pintype "bidirectional"))
      (node (ref "ETH1") (pin "8") (pinfunction "SHIELD-P8_8") (pintype "passive"))
      (node (ref "GND") (pin "TP") (pinfunction "P$1_TP") (pintype "bidirectional"))
      (node (ref "GND-3") (pin "TP") (pinfunction "P$1_TP") (pintype "bidirectional"))
      (node (ref "GND-5") (pin "TP") (pinfunction "P$1_TP") (pintype "bidirectional"))
      (node (ref "IC1") (pin "14") (pinfunction "AGND_14") (pintype "power_in"))
      (node (ref "IC1") (pin "16") (pinfunction "AGND_16") (pintype "power_in"))
      (node (ref "IC1") (pin "19") (pinfunction "AGND_19") (pintype "power_in"))
      (node (ref "IC1") (pin "29") (pinfunction "GND_29") (pintype "passive"))
      (node (ref "IC1") (pin "3") (pinfunction "AGND_3") (pintype "power_in"))
      (node (ref "IC1") (pin "48") (pinfunction "AGND_48") (pintype "power_in"))
      (node (ref "IC1") (pin "9") (pinfunction "AGND_9") (pintype "power_in"))
      (node (ref "IC2") (pin "19") (pinfunction "TESTEN_19") (pintype "bidirectional"))
      (node (ref "IC2") (pin "57") (pinfunction "GND_57") (pintype "bidirectional"))
      (node (ref "IC3") (pin "5") (pinfunction "V-_5") (pintype "power_in"))
      (node (ref "IC4") (pin "4") (pinfunction "GND_4") (pintype "power_in"))
      (node (ref "IC5") (pin "4") (pinfunction "GND_4") (pintype "bidirectional"))
      (node (ref "IC6") (pin "2") (pinfunction "A1_2") (pintype "bidirectional"))
      (node (ref "IC6") (pin "3") (pinfunction "A2_3") (pintype "bidirectional"))
      (node (ref "IC6") (pin "4") (pinfunction "GND_4") (pintype "power_in"))
      (node (ref "IC6") (pin "7") (pinfunction "WP_7") (pintype "bidirectional"))
      (node (ref "IC6") (pin "9") (pinfunction "GND_9") (pintype "power_in"))
      (node (ref "IC7") (pin "4") (pinfunction "GND_4") (pintype "bidirectional"))
      (node (ref "IC8") (pin "23") (pinfunction "VSS_23") (pintype "power_in"))
      (node (ref "IC8") (pin "25") (pinfunction "VSS_25") (pintype "power_in"))
      (node (ref "J1") (pin "13") (pinfunction "13_13") (pintype "bidirectional"))
      (node (ref "J2") (pin "1") (pinfunction "1_1") (pintype "bidirectional"))
      (node (ref "J2") (pin "13") (pinfunction "13_13") (pintype "bidirectional"))
      (node (ref "J2") (pin "14") (pinfunction "14_14") (pintype "bidirectional"))
      (node (ref "J2") (pin "2") (pinfunction "2_2") (pintype "bidirectional"))
      (node (ref "J3") (pin "1") (pinfunction "1_1") (pintype "bidirectional"))
      (node (ref "J3") (pin "13") (pinfunction "13_13") (pintype "bidirectional"))
      (node (ref "J3") (pin "14") (pinfunction "14_14") (pintype "bidirectional"))
      (node (ref "J3") (pin "2") (pinfunction "2_2") (pintype "bidirectional"))
      (node (ref "R11") (pin "1") (pinfunction "1_1") (pintype "passive"))
      (node (ref "R20") (pin "2") (pinfunction "2_2") (pintype "passive"))
      (node (ref "R23") (pin "2") (pinfunction "2_2") (pintype "passive"))
      (node (ref "R24") (pin "2") (pinfunction "2_2") (pintype "passive"))
      (node (ref "R26") (pin "2") (pinfunction "2_2") (pintype "passive"))
      (node (ref "R28") (pin "1") (pinfunction "1_1") (pintype "passive"))
      (node (ref "R32") (pin "2") (pinfunction "2_2") (pintype "passive"))
      (node (ref "R33") (pin "2") (pinfunction "2_2") (pintype "passive"))
      (node (ref "R37") (pin "2") (pinfunction "2_2") (pintype "passive"))
      (node (ref "R39") (pin "2") (pinfunction "2_2") (pintype "passive"))
      (node (ref "R44") (pin "2") (pinfunction "2_2") (pintype "passive"))
      (node (ref "R49") (pin "1") (pinfunction "1_1") (pintype "passive"))
      (node (ref "REF1") (pin "2") (pinfunction "A_2") (pintype "passive"))
      (node (ref "REF1") (pin "3") (pinfunction "A_3") (pintype "passive"))
      (node (ref "RESET") (pin "2") (pinfunction "S_2") (pintype "passive"))
      (node (ref "USBC") (pin "A1") (pinfunction "GND_A1") (pintype "passive"))
      (node (ref "USBC") (pin "A12") (pinfunction "GND1_A12") (pintype "passive"))
      (node (ref "USBC") (pin "B1") (pinfunction "GND3_B1") (pintype "passive"))
      (node (ref "USBC") (pin "B12") (pinfunction "GND2_B12") (pintype "passive"))
      (node (ref "USB_BOOT") (pin "2") (pinfunction "S_2") (pintype "passive"))
      (node (ref "X1") (pin "2") (pinfunction "VSS_2") (pintype "power_in"))
      (node (ref "X1") (pin "4") (pinfunction "VDD_4") (pintype "power_in"))
      (node (ref "X2") (pin "2") (pinfunction "VSS_2") (pintype "power_in"))
      (node (ref "X2") (pin "4") (pinfunction "VDD_4") (pintype "power_in"))
    )
    (net (code "15") (name "I2C0_SCL") (class "Default")
      (node (ref "IC2") (pin "7") (pinfunction "GPIO5_7") (pintype "bidirectional"))
      (node (ref "J3") (pin "7") (pinfunction "7_7") (pintype "bidirectional"))
      (node (ref "R38") (pin "1") (pinfunction "1_1") (pintype "passive"))
    )
    (net (code "16") (name "I2C0_SDA") (class "Default")
      (node (ref "IC2") (pin "6") (pinfunction "GPIO4_6") (pintype "bidirectional"))
      (node (ref "J3") (pin "5") (pinfunction "5_5") (pintype "bidirectional"))
      (node (ref "R38") (pin "2") (pinfunction "2_2") (pintype "passive"))
    )
    (net (code "17") (name "I2C1_SCL") (class "Default")
      (node (ref "IC2") (pin "5") (pinfunction "GPIO3_5") (pintype "bidirectional"))
      (node (ref "IC6") (pin "6") (pinfunction "SCL_6") (pintype "bidirectional"))
      (node (ref "R38") (pin "3") (pinfunction "3_3") (pintype "passive"))
    )
    (net (code "18") (name "I2C1_SDA") (class "Default")
      (node (ref "IC2") (pin "4") (pinfunction "GPIO2_4") (pintype "bidirectional"))
      (node (ref "IC6") (pin "5") (pinfunction "SDA_5") (pintype "bidirectional"))
      (node (ref "R38") (pin "4") (pinfunction "4_4") (pintype "passive"))
    )
    (net (code "19") (name "I_MEA{slash}TX") (class "Default")
      (node (ref "IC2") (pin "40") (pinfunction "GPIO28/ADC2_40") (pintype "bidirectional"))
      (node (ref "J1") (pin "4") (pinfunction "4_4") (pintype "bidirectional"))
      (node (ref "R46") (pin "1") (pinfunction "1_1") (pintype "passive"))
    )
    (net (code "20") (name "KEY_0") (class "Default")
      (node (ref "IC2") (pin "15") (pinfunction "GPIO12_15") (pintype "bidirectional"))
      (node (ref "J3") (pin "6") (pinfunction "6_6") (pintype "bidirectional"))
    )
    (net (code "21") (name "KEY_1") (class "Default")
      (node (ref "IC2") (pin "16") (pinfunction "GPIO13_16") (pintype "bidirectional"))
      (node (ref "J3") (pin "8") (pinfunction "8_8") (pintype "bidirectional"))
    )
    (net (code "22") (name "KEY_2") (class "Default")
      (node (ref "IC2") (pin "17") (pinfunction "GPIO14_17") (pintype "bidirectional"))
      (node (ref "J3") (pin "10") (pinfunction "10_10") (pintype "bidirectional"))
    )
    (net (code "23") (name "KEY_3") (class "Default")
      (node (ref "IC2") (pin "18") (pinfunction "GPIO15_18") (pintype "bidirectional"))
      (node (ref "J3") (pin "12") (pinfunction "12_12") (pintype "bidirectional"))
    )
    (net (code "24") (name "Net-(C5-Pad2)") (class "Default")
      (node (ref "C5") (pin "2") (pinfunction "2_2") (pintype "passive"))
      (node (ref "ETH1") (pin "S1") (pinfunction "SHIELD_S1") (pintype "passive"))
      (node (ref "ETH1") (pin "S2") (pinfunction "SHIELD_S2") (pintype "passive"))
    )
    (net (code "25") (name "Net-(C42-Pad1)") (class "Default")
      (node (ref "C42") (pin "1") (pinfunction "1_1") (pintype "passive"))
      (node (ref "R41") (pin "1") (pinfunction "1_1") (pintype "passive"))
    )
    (net (code "26") (name "Net-(C51-Pad1)") (class "Default")
      (node (ref "C51") (pin "1") (pinfunction "1_1") (pintype "passive"))
      (node (ref "R34") (pin "1") (pinfunction "1_1") (pintype "passive"))
    )
    (net (code "27") (name "Net-(ETH1-GK1)") (class "Default")
      (node (ref "ETH1") (pin "10") (pinfunction "GK1_10") (pintype "passive"))
      (node (ref "R9") (pin "2") (pinfunction "2_2") (pintype "passive"))
    )
    (net (code "28") (name "Net-(ETH1-GK2)") (class "Default")
      (node (ref "ETH1") (pin "12") (pinfunction "GK2_12") (pintype "passive"))
      (node (ref "R10") (pin "2") (pinfunction "2_2") (pintype "passive"))
    )
    (net (code "29") (name "Net-(IC1-1V2O)") (class "Default")
      (node (ref "C6") (pin "1") (pinfunction "1_1") (pintype "passive"))
      (node (ref "IC1") (pin "22") (pinfunction "1V2O_22") (pintype "output"))
    )
    (net (code "30") (name "Net-(IC1-EXRES1)") (class "Default")
      (node (ref "IC1") (pin "10") (pinfunction "EXRES1_10") (pintype "bidirectional"))
      (node (ref "R11") (pin "2") (pinfunction "2_2") (pintype "passive"))
    )
    (net (code "31") (name "Net-(IC1-TOCAP)") (class "Default")
      (node (ref "C7") (pin "1") (pinfunction "1_1") (pintype "passive"))
      (node (ref "IC1") (pin "20") (pinfunction "TOCAP_20") (pintype "output"))
    )
    (net (code "32") (name "Net-(IC1-XI)") (class "Default")
      (node (ref "IC1") (pin "30") (pinfunction "XI_30") (pintype "input"))
      (node (ref "R13") (pin "2") (pinfunction "2_2") (pintype "passive"))
    )
    (net (code "33") (name "Net-(IC1-XO)") (class "Default")
      (node (ref "IC1") (pin "31") (pinfunction "XO_31") (pintype "output"))
      (node (ref "R12") (pin "2") (pinfunction "2_2") (pintype "passive"))
    )
    (net (code "34") (name "Net-(IC2-RUN)") (class "Default")
      (node (ref "IC2") (pin "26") (pinfunction "RUN_26") (pintype "bidirectional"))
      (node (ref "R50") (pin "2") (pinfunction "2_2") (pintype "passive"))
      (node (ref "RESET") (pin "1") (pinfunction "P_1") (pintype "passive"))
    )
    (net (code "35") (name "Net-(IC2-USB_DM)") (class "Default")
      (node (ref "IC2") (pin "46") (pinfunction "USB_DM_46") (pintype "bidirectional"))
      (node (ref "R21") (pin "2") (pinfunction "2_2") (pintype "passive"))
    )
    (net (code "36") (name "Net-(IC2-USB_DP)") (class "Default")
      (node (ref "IC2") (pin "47") (pinfunction "USB_DP_47") (pintype "bidirectional"))
      (node (ref "R22") (pin "2") (pinfunction "2_2") (pintype "passive"))
    )
    (net (code "37") (name "Net-(IC3-+IN)") (class "Default")
      (node (ref "C21") (pin "1") (pinfunction "1_1") (pintype "passive"))
      (node (ref "C22") (pin "1") (pinfunction "1_1") (pintype "passive"))
      (node (ref "IC3") (pin "3") (pinfunction "+IN_3") (pintype "input"))
      (node (ref "R17") (pin "1") (pinfunction "1_1") (pintype "passive"))
      (node (ref "REF1") (pin "1") (pinfunction "C_1") (pintype "passive"))
      (node (ref "VREF") (pin "TP") (pinfunction "P$1_TP") (pintype "bidirectional"))
    )
    (net (code "38") (name "Net-(IC5-AAM)") (class "Default")
      (node (ref "IC5") (pin "1") (pinfunction "AAM_1") (pintype "bidirectional"))
      (node (ref "R32") (pin "1") (pinfunction "1_1") (pintype "passive"))
      (node (ref "R45") (pin "2") (pinfunction "2_2") (pintype "passive"))
    )
    (net (code "39") (name "Net-(IC5-BST)") (class "Default")
      (node (ref "IC5") (pin "5") (pinfunction "BST_5") (pintype "bidirectional"))
      (node (ref "R41") (pin "2") (pinfunction "2_2") (pintype "passive"))
    )
    (net (code "40") (name "Net-(IC5-EN)") (class "Default")
      (node (ref "IC5") (pin "6") (pinfunction "EN_6") (pintype "bidirectional"))
      (node (ref "R30") (pin "2") (pinfunction "2_2") (pintype "passive"))
    )
    (net (code "41") (name "Net-(IC5-FB)") (class "Default")
      (node (ref "IC5") (pin "8") (pinfunction "FB_8") (pintype "bidirectional"))
      (node (ref "R42") (pin "1") (pinfunction "1_1") (pintype "passive"))
    )
    (net (code "42") (name "Net-(IC5-SW)") (class "Default")
      (node (ref "C42") (pin "2") (pinfunction "2_2") (pintype "passive"))
      (node (ref "IC5") (pin "3") (pinfunction "SW_3") (pintype "bidirectional"))
      (node (ref "L3") (pin "1") (pinfunction "1_1") (pintype "passive"))
      (node (ref "SW3") (pin "TP") (pinfunction "P$1_TP") (pintype "bidirectional"))
    )
    (net (code "43") (name "Net-(IC5-VCC)") (class "Default")
      (node (ref "C40") (pin "1") (pinfunction "1_1") (pintype "passive"))
      (node (ref "IC5") (pin "7") (pinfunction "VCC_7") (pintype "bidirectional"))
      (node (ref "R45") (pin "1") (pinfunction "1_1") (pintype "passive"))
    )
    (net (code "44") (name "Net-(IC6-A0)") (class "Default")
      (node (ref "IC6") (pin "1") (pinfunction "A0_1") (pintype "bidirectional"))
      (node (ref "R27") (pin "1") (pinfunction "1_1") (pintype "passive"))
      (node (ref "R28") (pin "2") (pinfunction "2_2") (pintype "passive"))
    )
    (net (code "45") (name "Net-(IC7-AAM)") (class "Default")
      (node (ref "IC7") (pin "1") (pinfunction "AAM_1") (pintype "bidirectional"))
      (node (ref "R29") (pin "2") (pinfunction "2_2") (pintype "passive"))
      (node (ref "R33") (pin "1") (pinfunction "1_1") (pintype "passive"))
    )
    (net (code "46") (name "Net-(IC7-BST)") (class "Default")
      (node (ref "IC7") (pin "5") (pinfunction "BST_5") (pintype "bidirectional"))
      (node (ref "R34") (pin "2") (pinfunction "2_2") (pintype "passive"))
    )
    (net (code "47") (name "Net-(IC7-EN)") (class "Default")
      (node (ref "IC7") (pin "6") (pinfunction "EN_6") (pintype "bidirectional"))
      (node (ref "R31") (pin "2") (pinfunction "2_2") (pintype "passive"))
    )
    (net (code "48") (name "Net-(IC7-FB)") (class "Default")
      (node (ref "IC7") (pin "8") (pinfunction "FB_8") (pintype "bidirectional"))
      (node (ref "R35") (pin "1") (pinfunction "1_1") (pintype "passive"))
    )
    (net (code "49") (name "Net-(IC7-SW)") (class "Default")
      (node (ref "C51") (pin "2") (pinfunction "2_2") (pintype "passive"))
      (node (ref "IC7") (pin "3") (pinfunction "SW_3") (pintype "bidirectional"))
      (node (ref "L2") (pin "1") (pinfunction "1_1") (pintype "passive"))
      (node (ref "SW5") (pin "TP") (pinfunction "P$1_TP") (pintype "bidirectional"))
    )
    (net (code "50") (name "Net-(IC7-VCC)") (class "Default")
      (node (ref "C49") (pin "1") (pinfunction "1_1") (pintype "passive"))
      (node (ref "IC7") (pin "7") (pinfunction "VCC_7") (pintype "bidirectional"))
      (node (ref "R29") (pin "1") (pinfunction "1_1") (pintype "passive"))
    )
    (net (code "51") (name "Net-(VFB3-P$1)") (class "Default")
      (node (ref "C43") (pin "2") (pinfunction "2_2") (pintype "passive"))
      (node (ref "R42") (pin "2") (pinfunction "2_2") (pintype "passive"))
      (node (ref "R43") (pin "2") (pinfunction "2_2") (pintype "passive"))
      (node (ref "R44") (pin "1") (pinfunction "1_1") (pintype "passive"))
      (node (ref "VFB3") (pin "TP") (pinfunction "P$1_TP") (pintype "bidirectional"))
    )
    (net (code "52") (name "Net-(VFB5-P$1)") (class "Default")
      (node (ref "C52") (pin "2") (pinfunction "2_2") (pintype "passive"))
      (node (ref "R35") (pin "2") (pinfunction "2_2") (pintype "passive"))
      (node (ref "R36") (pin "2") (pinfunction "2_2") (pintype "passive"))
      (node (ref "R37") (pin "1") (pinfunction "1_1") (pintype "passive"))
      (node (ref "VFB5") (pin "TP") (pinfunction "P$1_TP") (pintype "bidirectional"))
    )
    (net (code "53") (name "Net-(X1-CON)") (class "Default")
      (node (ref "C8") (pin "1") (pinfunction "1_1") (pintype "passive"))
      (node (ref "R12") (pin "1") (pinfunction "1_1") (pintype "passive"))
      (node (ref "X1") (pin "1") (pinfunction "CON_1") (pintype "input"))
    )
    (net (code "54") (name "Net-(X1-OUT)") (class "Default")
      (node (ref "C9") (pin "1") (pinfunction "1_1") (pintype "passive"))
      (node (ref "R13") (pin "1") (pinfunction "1_1") (pintype "passive"))
      (node (ref "X1") (pin "3") (pinfunction "OUT_3") (pintype "output"))
    )
    (net (code "55") (name "Net-(X2-OUT)") (class "Default")
      (node (ref "C20") (pin "1") (pinfunction "1_1") (pintype "passive"))
      (node (ref "R15") (pin "2") (pinfunction "2_2") (pintype "passive"))
      (node (ref "R16") (pin "1") (pinfunction "1_1") (pintype "passive"))
      (node (ref "X2") (pin "3") (pinfunction "OUT_3") (pintype "output"))
    )
    (net (code "56") (name "PWR_DETECT") (class "Default")
      (node (ref "12VFB") (pin "TP") (pinfunction "P$1_TP") (pintype "bidirectional"))
      (node (ref "IC2") (pin "41") (pinfunction "GPIO29/ADC3_41") (pintype "bidirectional"))
      (node (ref "R48") (pin "1") (pinfunction "1_1") (pintype "passive"))
      (node (ref "R49") (pin "2") (pinfunction "2_2") (pintype "passive"))
    )
    (net (code "57") (name "QSPI_SCLK") (class "Default")
      (node (ref "IC2") (pin "52") (pinfunction "QSPI_SCLK_52") (pintype "bidirectional"))
      (node (ref "IC4") (pin "6") (pinfunction "CLK_6") (pintype "bidirectional"))
    )
    (net (code "58") (name "QSPI_SD0") (class "Default")
      (node (ref "IC2") (pin "53") (pinfunction "QSPI_SD0_53") (pintype "bidirectional"))
      (node (ref "IC4") (pin "5") (pinfunction "DI/IO0_5") (pintype "bidirectional"))
    )
    (net (code "59") (name "QSPI_SD1") (class "Default")
      (node (ref "IC2") (pin "55") (pinfunction "QSPI_SD1_55") (pintype "bidirectional"))
      (node (ref "IC4") (pin "2") (pinfunction "DO/IO1_2") (pintype "bidirectional"))
    )
    (net (code "60") (name "QSPI_SD2") (class "Default")
      (node (ref "IC2") (pin "54") (pinfunction "QSPI_SD2_54") (pintype "bidirectional"))
      (node (ref "IC4") (pin "3") (pinfunction "~{WP}/IO2_3") (pintype "bidirectional"))
    )
    (net (code "61") (name "QSPI_SD3") (class "Default")
      (node (ref "IC2") (pin "51") (pinfunction "QSPI_SD3_51") (pintype "bidirectional"))
      (node (ref "IC4") (pin "7") (pinfunction "~{HOLD}/IO3_7") (pintype "bidirectional"))
    )
    (net (code "62") (name "RCT") (class "Default")
      (node (ref "C1") (pin "1") (pinfunction "1_1") (pintype "passive"))
      (node (ref "ETH1") (pin "5") (pinfunction "RCT_5") (pintype "passive"))
      (node (ref "R5") (pin "1") (pinfunction "1_1") (pintype "passive"))
      (node (ref "R6") (pin "1") (pinfunction "1_1") (pintype "passive"))
    )
    (net (code "63") (name "RDC_RD_N") (class "Default")
      (node (ref "C3") (pin "1") (pinfunction "1_1") (pintype "passive"))
      (node (ref "R4") (pin "2") (pinfunction "2_2") (pintype "passive"))
      (node (ref "R5") (pin "2") (pinfunction "2_2") (pintype "passive"))
    )
    (net (code "64") (name "RDC_RD_P") (class "Default")
      (node (ref "C4") (pin "1") (pinfunction "1_1") (pintype "passive"))
      (node (ref "R3") (pin "2") (pinfunction "2_2") (pintype "passive"))
      (node (ref "R6") (pin "2") (pinfunction "2_2") (pintype "passive"))
    )
    (net (code "65") (name "RD_N") (class "Default")
      (node (ref "C3") (pin "2") (pinfunction "2_2") (pintype "passive"))
      (node (ref "ETH1") (pin "6") (pinfunction "RD-_6") (pintype "passive"))
    )
    (net (code "66") (name "RD_P") (class "Default")
      (node (ref "C4") (pin "2") (pinfunction "2_2") (pintype "passive"))
      (node (ref "ETH1") (pin "4") (pinfunction "RD+_4") (pintype "passive"))
    )
    (net (code "67") (name "REL_0") (class "Default")
      (node (ref "IC8") (pin "15") (pinfunction "GPA0_15") (pintype "bidirectional"))
      (node (ref "J1") (pin "12") (pinfunction "12_12") (pintype "bidirectional"))
    )
    (net (code "68") (name "REL_1") (class "Default")
      (node (ref "IC8") (pin "16") (pinfunction "GPA1_16") (pintype "bidirectional"))
      (node (ref "J1") (pin "11") (pinfunction "11_11") (pintype "bidirectional"))
    )
    (net (code "69") (name "REL_2") (class "Default")
      (node (ref "IC8") (pin "17") (pinfunction "GPA2_17") (pintype "bidirectional"))
      (node (ref "J1") (pin "10") (pinfunction "10_10") (pintype "bidirectional"))
    )
    (net (code "70") (name "REL_3") (class "Default")
      (node (ref "IC8") (pin "18") (pinfunction "GPA3_18") (pintype "bidirectional"))
      (node (ref "J1") (pin "9") (pinfunction "9_9") (pintype "bidirectional"))
    )
    (net (code "71") (name "REL_4") (class "Default")
      (node (ref "IC8") (pin "19") (pinfunction "GPA4_19") (pintype "bidirectional"))
      (node (ref "J1") (pin "8") (pinfunction "8_8") (pintype "bidirectional"))
    )
    (net (code "72") (name "REL_5") (class "Default")
      (node (ref "IC8") (pin "20") (pinfunction "GPA5_20") (pintype "bidirectional"))
      (node (ref "J1") (pin "7") (pinfunction "7_7") (pintype "bidirectional"))
    )
    (net (code "73") (name "REL_6") (class "Default")
      (node (ref "IC8") (pin "21") (pinfunction "GPA6_21") (pintype "bidirectional"))
      (node (ref "J1") (pin "6") (pinfunction "6_6") (pintype "bidirectional"))
    )
    (net (code "74") (name "REL_7") (class "Default")
      (node (ref "IC8") (pin "22") (pinfunction "GPA7_22") (pintype "bidirectional"))
      (node (ref "J1") (pin "5") (pinfunction "5_5") (pintype "bidirectional"))
    )
    (net (code "75") (name "RP_XI") (class "Default")
      (node (ref "C19") (pin "1") (pinfunction "1_1") (pintype "passive"))
      (node (ref "IC2") (pin "20") (pinfunction "XIN_20") (pintype "bidirectional"))
      (node (ref "R15") (pin "1") (pinfunction "1_1") (pintype "passive"))
      (node (ref "X2") (pin "1") (pinfunction "CON_1") (pintype "input"))
    )
    (net (code "76") (name "RP_XO") (class "Default")
      (node (ref "IC2") (pin "21") (pinfunction "XOUT_21") (pintype "bidirectional"))
      (node (ref "R16") (pin "2") (pinfunction "2_2") (pintype "passive"))
    )
    (net (code "77") (name "RX_RD_N") (class "Default")
      (node (ref "IC1") (pin "5") (pinfunction "RXN_5") (pintype "input"))
      (node (ref "R4") (pin "1") (pinfunction "1_1") (pintype "passive"))
    )
    (net (code "78") (name "RX_RD_P") (class "Default")
      (node (ref "IC1") (pin "6") (pinfunction "RXP_6") (pintype "input"))
      (node (ref "R3") (pin "1") (pinfunction "1_1") (pintype "passive"))
    )
    (net (code "79") (name "SPI0_MISO") (class "Default")
      (node (ref "IC1") (pin "34") (pinfunction "MISO_34") (pintype "output"))
      (node (ref "IC2") (pin "27") (pinfunction "GPIO16_27") (pintype "bidirectional"))
    )
    (net (code "80") (name "SPI0_MOSI") (class "Default")
      (node (ref "IC1") (pin "35") (pinfunction "MOSI_35") (pintype "input"))
      (node (ref "IC2") (pin "30") (pinfunction "GPIO19_30") (pintype "bidirectional"))
    )
    (net (code "81") (name "SPI0_SCK") (class "Default")
      (node (ref "IC1") (pin "33") (pinfunction "SCLK_33") (pintype "input"))
      (node (ref "IC2") (pin "29") (pinfunction "GPIO18_29") (pintype "bidirectional"))
    )
    (net (code "82") (name "SPI1_MISO") (class "Default")
      (node (ref "IC2") (pin "11") (pinfunction "GPIO8_11") (pintype "bidirectional"))
      (node (ref "IC8") (pin "12") (pinfunction "SO_12") (pintype "output"))
      (node (ref "J2") (pin "7") (pinfunction "7_7") (pintype "bidirectional"))
    )
    (net (code "83") (name "SPI1_MOSI") (class "Default")
      (node (ref "IC2") (pin "14") (pinfunction "GPIO11_14") (pintype "bidirectional"))
      (node (ref "IC8") (pin "11") (pinfunction "SI_11") (pintype "input"))
      (node (ref "J2") (pin "5") (pinfunction "5_5") (pintype "bidirectional"))
    )
    (net (code "84") (name "SPI1_SCK") (class "Default")
      (node (ref "IC2") (pin "13") (pinfunction "GPIO10_13") (pintype "bidirectional"))
      (node (ref "IC8") (pin "10") (pinfunction "SCK_10") (pintype "input"))
      (node (ref "J2") (pin "9") (pinfunction "9_9") (pintype "bidirectional"))
    )
    (net (code "85") (name "SWCLK") (class "Default")
      (node (ref "DBG2") (pin "1") (pinfunction "P$1_1") (pintype "bidirectional"))
      (node (ref "IC2") (pin "24") (pinfunction "SWCLK_24") (pintype "bidirectional"))
    )
    (net (code "86") (name "SWDIO") (class "Default")
      (node (ref "DBG2") (pin "3") (pinfunction "P$3_3") (pintype "bidirectional"))
      (node (ref "IC2") (pin "25") (pinfunction "SWDIO_25") (pintype "bidirectional"))
    )
    (net (code "87") (name "TCT") (class "Default")
      (node (ref "C2") (pin "1") (pinfunction "1_1") (pintype "passive"))
      (node (ref "ETH1") (pin "2") (pinfunction "TCT_2") (pintype "passive"))
      (node (ref "R40") (pin "1") (pinfunction "1_1") (pintype "passive"))
    )
    (net (code "88") (name "TD_N") (class "Default")
      (node (ref "ETH1") (pin "3") (pinfunction "TD-_3") (pintype "passive"))
      (node (ref "R1") (pin "2") (pinfunction "2_2") (pintype "passive"))
      (node (ref "R8") (pin "1") (pinfunction "1_1") (pintype "passive"))
    )
    (net (code "89") (name "TD_P") (class "Default")
      (node (ref "ETH1") (pin "1") (pinfunction "TD+_1") (pintype "passive"))
      (node (ref "R2") (pin "2") (pinfunction "2_2") (pintype "passive"))
      (node (ref "R7") (pin "1") (pinfunction "1_1") (pintype "passive"))
    )
    (net (code "90") (name "TX_TD_N") (class "Default")
      (node (ref "IC1") (pin "1") (pinfunction "TXN_1") (pintype "output"))
      (node (ref "R1") (pin "1") (pinfunction "1_1") (pintype "passive"))
    )
    (net (code "91") (name "TX_TD_P") (class "Default")
      (node (ref "IC1") (pin "2") (pinfunction "TXP_2") (pintype "output"))
      (node (ref "R2") (pin "1") (pinfunction "1_1") (pintype "passive"))
    )
    (net (code "92") (name "UART0_RX") (class "Default")
      (node (ref "DBG1") (pin "1") (pinfunction "P$1_1") (pintype "bidirectional"))
      (node (ref "IC2") (pin "2") (pinfunction "GPIO0_2") (pintype "bidirectional"))
      (node (ref "R47") (pin "2") (pinfunction "2_2") (pintype "passive"))
    )
    (net (code "93") (name "UART0_TX") (class "Default")
      (node (ref "DBG1") (pin "3") (pinfunction "P$3_3") (pintype "bidirectional"))
      (node (ref "IC2") (pin "3") (pinfunction "GPIO1_3") (pintype "bidirectional"))
      (node (ref "R46") (pin "2") (pinfunction "2_2") (pintype "passive"))
    )
    (net (code "94") (name "USB_BOOT") (class "Default")
      (node (ref "R19") (pin "1") (pinfunction "1_1") (pintype "passive"))
      (node (ref "USB_BOOT") (pin "1") (pinfunction "P_1") (pintype "passive"))
    )
    (net (code "95") (name "USB_SHIELD") (class "Default")
      (node (ref "C54") (pin "1") (pinfunction "1_1") (pintype "passive"))
      (node (ref "R39") (pin "1") (pinfunction "1_1") (pintype "passive"))
      (node (ref "USBC") (pin "S1") (pinfunction "SHIELD_S1") (pintype "passive"))
      (node (ref "USBC") (pin "S2") (pinfunction "SHIELD_S2") (pintype "passive"))
      (node (ref "USBC") (pin "S3") (pinfunction "SHIELD_S3") (pintype "passive"))
      (node (ref "USBC") (pin "S4") (pinfunction "SHIELD_S4") (pintype "passive"))
    )
    (net (code "96") (name "VBUS") (class "Default")
      (node (ref "C26") (pin "1") (pinfunction "1_1") (pintype "passive"))
      (node (ref "C27") (pin "1") (pinfunction "1_1") (pintype "passive"))
      (node (ref "ESD1") (pin "4") (pinfunction "C3_4") (pintype "bidirectional"))
      (node (ref "R20") (pin "1") (pinfunction "1_1") (pintype "passive"))
      (node (ref "R25") (pin "1") (pinfunction "1_1") (pintype "passive"))
      (node (ref "USBC") (pin "A4") (pinfunction "VBUS_A4") (pintype "passive"))
      (node (ref "USBC") (pin "A9") (pinfunction "VBUS1_A9") (pintype "passive"))
      (node (ref "USBC") (pin "B4") (pinfunction "VBUS3_B4") (pintype "passive"))
      (node (ref "USBC") (pin "B9") (pinfunction "VBUS2_B9") (pintype "passive"))
      (node (ref "VBUS") (pin "TP") (pinfunction "P$1_TP") (pintype "bidirectional"))
    )
    (net (code "97") (name "V_MEA{slash}RX") (class "Default")
      (node (ref "IC2") (pin "39") (pinfunction "GPIO27/ADC1_39") (pintype "bidirectional"))
      (node (ref "J1") (pin "3") (pinfunction "3_3") (pintype "bidirectional"))
      (node (ref "R47") (pin "1") (pinfunction "1_1") (pintype "passive"))
    )
    (net (code "98") (name "V_USB") (class "Default")
      (node (ref "IC2") (pin "38") (pinfunction "GPIO26/ADC0_38") (pintype "bidirectional"))
      (node (ref "R25") (pin "2") (pinfunction "2_2") (pintype "passive"))
      (node (ref "R26") (pin "1") (pinfunction "1_1") (pintype "passive"))
    )
    (net (code "99") (name "unconnected-(IC1-DNC-Pad7)") (class "Default")
      (node (ref "IC1") (pin "7") (pinfunction "DNC_7") (pintype "bidirectional"))
    )
    (net (code "100") (name "unconnected-(IC1-DUPLED-Pad26)") (class "Default")
      (node (ref "IC1") (pin "26") (pinfunction "DUPLED_26") (pintype "output"))
    )
    (net (code "101") (name "unconnected-(IC1-RSVD1-Pad23)") (class "Default")
      (node (ref "IC1") (pin "23") (pinfunction "RSVD1_23") (pintype "input"))
    )
    (net (code "102") (name "unconnected-(IC1-RSVD2-Pad38)") (class "Default")
      (node (ref "IC1") (pin "38") (pinfunction "RSVD2_38") (pintype "input"))
    )
    (net (code "103") (name "unconnected-(IC1-RSVD3-Pad39)") (class "Default")
      (node (ref "IC1") (pin "39") (pinfunction "RSVD3_39") (pintype "input"))
    )
    (net (code "104") (name "unconnected-(IC1-RSVD4-Pad40)") (class "Default")
      (node (ref "IC1") (pin "40") (pinfunction "RSVD4_40") (pintype "input"))
    )
    (net (code "105") (name "unconnected-(IC1-RSVD5-Pad41)") (class "Default")
      (node (ref "IC1") (pin "41") (pinfunction "RSVD5_41") (pintype "input"))
    )
    (net (code "106") (name "unconnected-(IC1-RSVD6-Pad42)") (class "Default")
      (node (ref "IC1") (pin "42") (pinfunction "RSVD6_42") (pintype "input"))
    )
    (net (code "107") (name "unconnected-(IC1-SPDLED-Pad24)") (class "Default")
      (node (ref "IC1") (pin "24") (pinfunction "SPDLED_24") (pintype "output"))
    )
    (net (code "108") (name "unconnected-(IC1-VBG-Pad18)") (class "Default")
      (node (ref "IC1") (pin "18") (pinfunction "VBG_18") (pintype "output"))
    )
    (net (code "109") (name "unconnected-(IC2-GPIO24-Pad36)") (class "Default")
      (node (ref "IC2") (pin "36") (pinfunction "GPIO24_36") (pintype "bidirectional"))
    )
    (net (code "110") (name "unconnected-(IC2-GPIO25-Pad37)") (class "Default")
      (node (ref "IC2") (pin "37") (pinfunction "GPIO25_37") (pintype "bidirectional"))
    )
    (net (code "111") (name "unconnected-(IC8-GPB0-Pad24)") (class "Default")
      (node (ref "IC8") (pin "24") (pinfunction "GPB0_24") (pintype "bidirectional"))
    )
    (net (code "112") (name "unconnected-(IC8-GPB1-Pad1)") (class "Default")
      (node (ref "IC8") (pin "1") (pinfunction "GPB1_1") (pintype "bidirectional"))
    )
    (net (code "113") (name "unconnected-(IC8-GPB2-Pad2)") (class "Default")
      (node (ref "IC8") (pin "2") (pinfunction "GPB2_2") (pintype "bidirectional"))
    )
    (net (code "114") (name "unconnected-(IC8-GPB3-Pad3)") (class "Default")
      (node (ref "IC8") (pin "3") (pinfunction "GPB3_3") (pintype "bidirectional"))
    )
    (net (code "115") (name "unconnected-(IC8-GPB4-Pad4)") (class "Default")
      (node (ref "IC8") (pin "4") (pinfunction "GPB4_4") (pintype "bidirectional"))
    )
    (net (code "116") (name "unconnected-(IC8-GPB5-Pad5)") (class "Default")
      (node (ref "IC8") (pin "5") (pinfunction "GPB5_5") (pintype "bidirectional"))
    )
    (net (code "117") (name "unconnected-(IC8-GPB6-Pad6)") (class "Default")
      (node (ref "IC8") (pin "6") (pinfunction "GPB6_6") (pintype "bidirectional"))
    )
    (net (code "118") (name "unconnected-(IC8-GPB7-Pad7)") (class "Default")
      (node (ref "IC8") (pin "7") (pinfunction "GPB7_7") (pintype "bidirectional"))
    )
    (net (code "119") (name "unconnected-(IC8-INTA-Pad14)") (class "Default")
      (node (ref "IC8") (pin "14") (pinfunction "INTA_14") (pintype "output"))
    )
    (net (code "120") (name "unconnected-(J2-Pad6)") (class "Default")
      (node (ref "J2") (pin "6") (pinfunction "6_6") (pintype "bidirectional"))
    )
    (net (code "121") (name "unconnected-(J2-Pad8)") (class "Default")
      (node (ref "J2") (pin "8") (pinfunction "8_8") (pintype "bidirectional"))
    )
    (net (code "122") (name "unconnected-(J2-Pad10)") (class "Default")
      (node (ref "J2") (pin "10") (pinfunction "10_10") (pintype "bidirectional"))
    )
    (net (code "123") (name "unconnected-(J2-Pad12)") (class "Default")
      (node (ref "J2") (pin "12") (pinfunction "12_12") (pintype "bidirectional"))
    )
    (net (code "124") (name "unconnected-(USBC-SBU1-PadA8)") (class "Default")
      (node (ref "USBC") (pin "A8") (pinfunction "SBU1_A8") (pintype "passive"))
    )
    (net (code "125") (name "unconnected-(USBC-SBU2-PadB8)") (class "Default")
      (node (ref "USBC") (pin "B8") (pinfunction "SBU2_B8") (pintype "passive"))
    )
    (net (code "126") (name "~{ACT}") (class "Default")
      (node (ref "IC1") (pin "27") (pinfunction "ACTLED_27") (pintype "output"))
      (node (ref "R10") (pin "1") (pinfunction "1_1") (pintype "passive"))
    )
    (net (code "127") (name "~{INT}") (class "Default")
      (node (ref "IC1") (pin "36") (pinfunction "~{INTN}_36") (pintype "input"))
      (node (ref "IC2") (pin "32") (pinfunction "GPIO21_32") (pintype "bidirectional"))
    )
    (net (code "128") (name "~{LINK}") (class "Default")
      (node (ref "IC1") (pin "25") (pinfunction "LINKLED_25") (pintype "output"))
      (node (ref "R9") (pin "1") (pinfunction "1_1") (pintype "passive"))
    )
    (net (code "129") (name "~{QSPI_SS}") (class "Default")
      (node (ref "IC2") (pin "56") (pinfunction "QSPI_SS_N_56") (pintype "bidirectional"))
      (node (ref "IC4") (pin "1") (pinfunction "~{CS}_1") (pintype "bidirectional"))
      (node (ref "R18") (pin "1") (pinfunction "1_1") (pintype "passive"))
      (node (ref "R19") (pin "2") (pinfunction "2_2") (pintype "passive"))
    )
    (net (code "130") (name "~{RST}") (class "Default")
      (node (ref "IC1") (pin "37") (pinfunction "~{RSTN}_37") (pintype "input"))
      (node (ref "IC2") (pin "31") (pinfunction "GPIO20_31") (pintype "bidirectional"))
      (node (ref "R14") (pin "1") (pinfunction "1_1") (pintype "passive"))
    )
    (net (code "131") (name "~{SPI0_CS}") (class "Default")
      (node (ref "IC1") (pin "32") (pinfunction "~{SCSN}_32") (pintype "input"))
      (node (ref "IC2") (pin "28") (pinfunction "GPIO17_28") (pintype "bidirectional"))
    )
    (net (code "132") (name "~{SPI1_CS_S}") (class "Default")
      (node (ref "IC2") (pin "8") (pinfunction "GPIO6_8") (pintype "bidirectional"))
      (node (ref "J2") (pin "11") (pinfunction "11_11") (pintype "bidirectional"))
    )
    (net (code "133") (name "~{SPI1_CS}") (class "Default")
      (node (ref "IC2") (pin "12") (pinfunction "GPIO9_12") (pintype "bidirectional"))
      (node (ref "IC8") (pin "9") (pinfunction "~{CS}_9") (pintype "input"))
    )
  )
)
